# matrix.net
KiCad netlist of a schematic drawn in Altium Designer
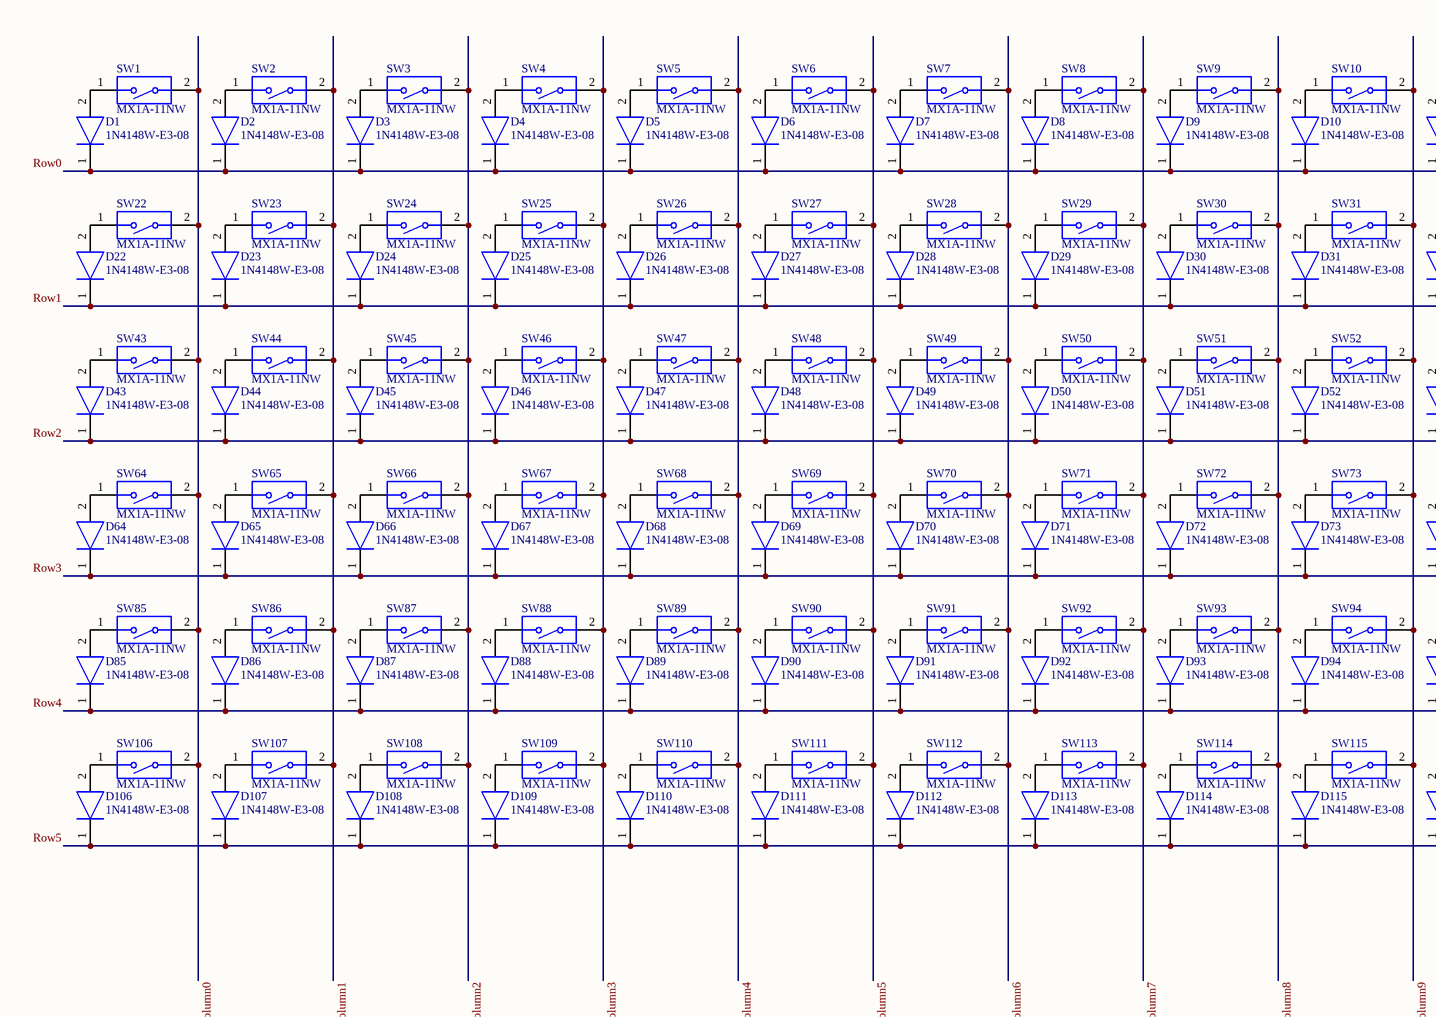
[diagram p0: matrix.SchDoc, left]
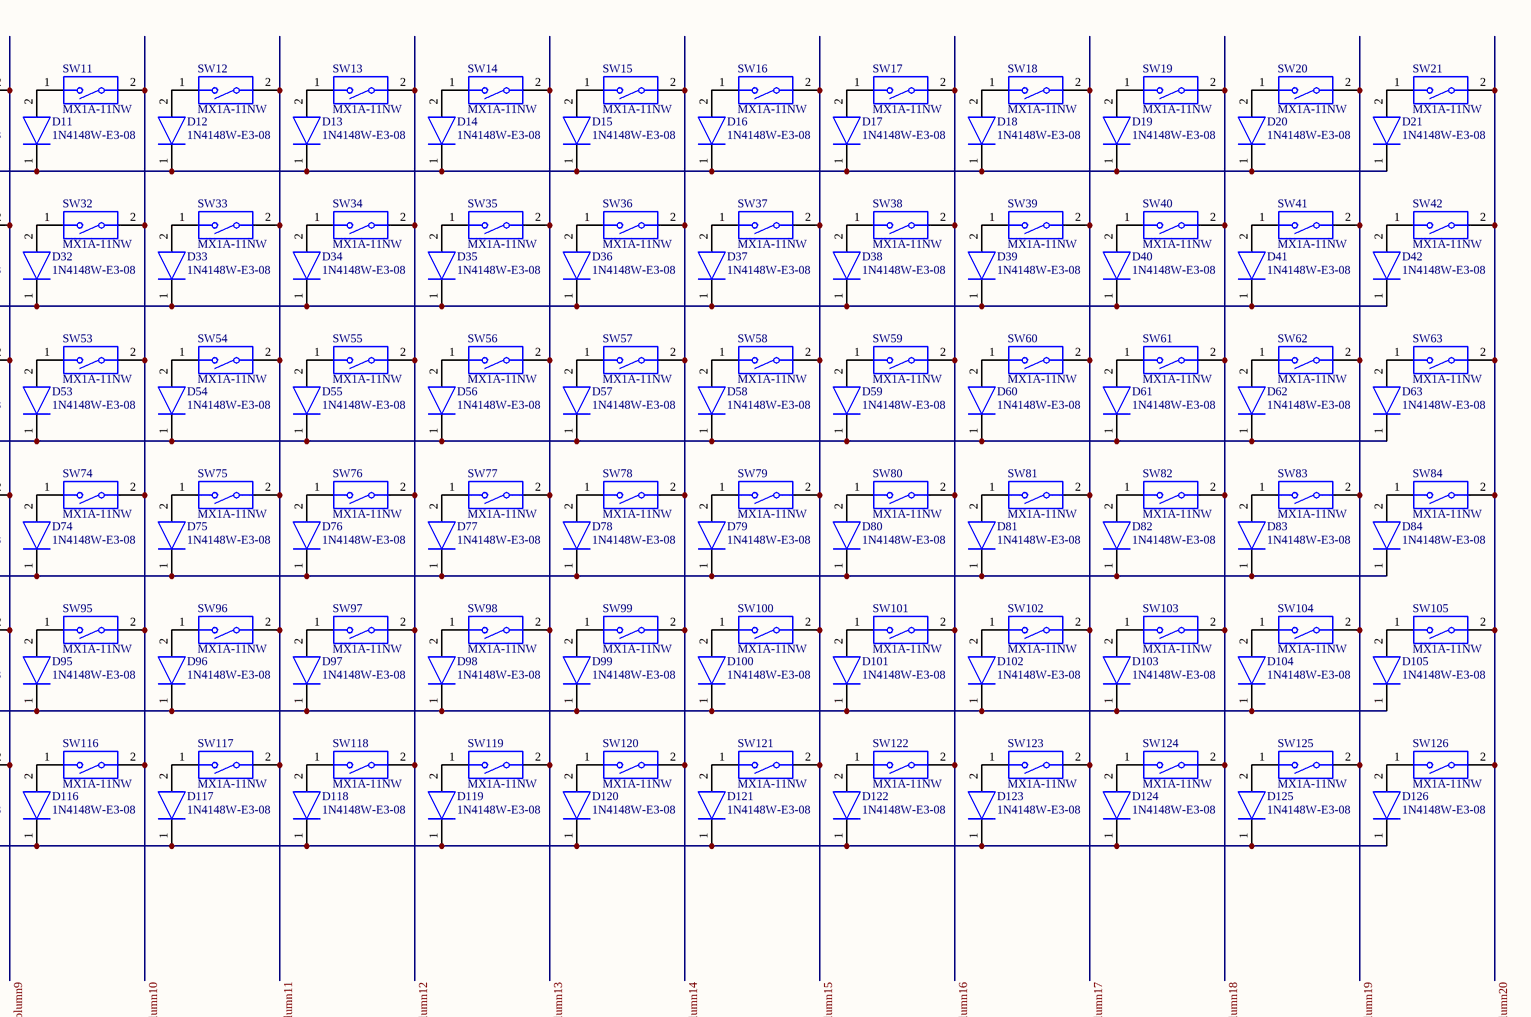
[diagram p1: matrix.SchDoc, right]

(export (version "E")
  (design (tool "Eeschema 10.0.6"))
  (components
    (comp (ref "D1")
      (value "1N4148W-E3-08")
      (footprint "SamacSys:SOD3716X135N")
      (description "Diode")
      (fields (field (name "MOUSER PART NUMBER") "78-1N4148W-E3-08"))
      (libsource (lib "*") (part "1N4148W-E3-08"))
    )
    (comp (ref "D2")
      (value "1N4148W-E3-08")
      (footprint "SamacSys:SOD3716X135N")
      (description "Diode")
      (fields (field (name "MOUSER PART NUMBER") "78-1N4148W-E3-08"))
      (libsource (lib "*") (part "1N4148W-E3-08"))
    )
    (comp (ref "D3")
      (value "1N4148W-E3-08")
      (footprint "SamacSys:SOD3716X135N")
      (description "Diode")
      (fields (field (name "MOUSER PART NUMBER") "78-1N4148W-E3-08"))
      (libsource (lib "*") (part "1N4148W-E3-08"))
    )
    (comp (ref "D4")
      (value "1N4148W-E3-08")
      (footprint "SamacSys:SOD3716X135N")
      (description "Diode")
      (fields (field (name "MOUSER PART NUMBER") "78-1N4148W-E3-08"))
      (libsource (lib "*") (part "1N4148W-E3-08"))
    )
    (comp (ref "D5")
      (value "1N4148W-E3-08")
      (footprint "SamacSys:SOD3716X135N")
      (description "Diode")
      (fields (field (name "MOUSER PART NUMBER") "78-1N4148W-E3-08"))
      (libsource (lib "*") (part "1N4148W-E3-08"))
    )
    (comp (ref "D6")
      (value "1N4148W-E3-08")
      (footprint "SamacSys:SOD3716X135N")
      (description "Diode")
      (fields (field (name "MOUSER PART NUMBER") "78-1N4148W-E3-08"))
      (libsource (lib "*") (part "1N4148W-E3-08"))
    )
    (comp (ref "D7")
      (value "1N4148W-E3-08")
      (footprint "SamacSys:SOD3716X135N")
      (description "Diode")
      (fields (field (name "MOUSER PART NUMBER") "78-1N4148W-E3-08"))
      (libsource (lib "*") (part "1N4148W-E3-08"))
    )
    (comp (ref "D8")
      (value "1N4148W-E3-08")
      (footprint "SamacSys:SOD3716X135N")
      (description "Diode")
      (fields (field (name "MOUSER PART NUMBER") "78-1N4148W-E3-08"))
      (libsource (lib "*") (part "1N4148W-E3-08"))
    )
    (comp (ref "D9")
      (value "1N4148W-E3-08")
      (footprint "SamacSys:SOD3716X135N")
      (description "Diode")
      (fields (field (name "MOUSER PART NUMBER") "78-1N4148W-E3-08"))
      (libsource (lib "*") (part "1N4148W-E3-08"))
    )
    (comp (ref "D10")
      (value "1N4148W-E3-08")
      (footprint "SamacSys:SOD3716X135N")
      (description "Diode")
      (fields (field (name "MOUSER PART NUMBER") "78-1N4148W-E3-08"))
      (libsource (lib "*") (part "1N4148W-E3-08"))
    )
    (comp (ref "D11")
      (value "1N4148W-E3-08")
      (footprint "SamacSys:SOD3716X135N")
      (description "Diode")
      (fields (field (name "MOUSER PART NUMBER") "78-1N4148W-E3-08"))
      (libsource (lib "*") (part "1N4148W-E3-08"))
    )
    (comp (ref "D12")
      (value "1N4148W-E3-08")
      (footprint "SamacSys:SOD3716X135N")
      (description "Diode")
      (fields (field (name "MOUSER PART NUMBER") "78-1N4148W-E3-08"))
      (libsource (lib "*") (part "1N4148W-E3-08"))
    )
    (comp (ref "D13")
      (value "1N4148W-E3-08")
      (footprint "SamacSys:SOD3716X135N")
      (description "Diode")
      (fields (field (name "MOUSER PART NUMBER") "78-1N4148W-E3-08"))
      (libsource (lib "*") (part "1N4148W-E3-08"))
    )
    (comp (ref "D14")
      (value "1N4148W-E3-08")
      (footprint "SamacSys:SOD3716X135N")
      (description "Diode")
      (fields (field (name "MOUSER PART NUMBER") "78-1N4148W-E3-08"))
      (libsource (lib "*") (part "1N4148W-E3-08"))
    )
    (comp (ref "D15")
      (value "1N4148W-E3-08")
      (footprint "SamacSys:SOD3716X135N")
      (description "Diode")
      (fields (field (name "MOUSER PART NUMBER") "78-1N4148W-E3-08"))
      (libsource (lib "*") (part "1N4148W-E3-08"))
    )
    (comp (ref "D16")
      (value "1N4148W-E3-08")
      (footprint "SamacSys:SOD3716X135N")
      (description "Diode")
      (fields (field (name "MOUSER PART NUMBER") "78-1N4148W-E3-08"))
      (libsource (lib "*") (part "1N4148W-E3-08"))
    )
    (comp (ref "D17")
      (value "1N4148W-E3-08")
      (footprint "SamacSys:SOD3716X135N")
      (description "Diode")
      (fields (field (name "MOUSER PART NUMBER") "78-1N4148W-E3-08"))
      (libsource (lib "*") (part "1N4148W-E3-08"))
    )
    (comp (ref "D18")
      (value "1N4148W-E3-08")
      (footprint "SamacSys:SOD3716X135N")
      (description "Diode")
      (fields (field (name "MOUSER PART NUMBER") "78-1N4148W-E3-08"))
      (libsource (lib "*") (part "1N4148W-E3-08"))
    )
    (comp (ref "D19")
      (value "1N4148W-E3-08")
      (footprint "SamacSys:SOD3716X135N")
      (description "Diode")
      (fields (field (name "MOUSER PART NUMBER") "78-1N4148W-E3-08"))
      (libsource (lib "*") (part "1N4148W-E3-08"))
    )
    (comp (ref "D20")
      (value "1N4148W-E3-08")
      (footprint "SamacSys:SOD3716X135N")
      (description "Diode")
      (fields (field (name "MOUSER PART NUMBER") "78-1N4148W-E3-08"))
      (libsource (lib "*") (part "1N4148W-E3-08"))
    )
    (comp (ref "D21")
      (value "1N4148W-E3-08")
      (footprint "SamacSys:SOD3716X135N")
      (description "Diode")
      (fields (field (name "MOUSER PART NUMBER") "78-1N4148W-E3-08"))
      (libsource (lib "*") (part "1N4148W-E3-08"))
    )
    (comp (ref "D22")
      (value "1N4148W-E3-08")
      (footprint "SamacSys:SOD3716X135N")
      (description "Diode")
      (fields (field (name "MOUSER PART NUMBER") "78-1N4148W-E3-08"))
      (libsource (lib "*") (part "1N4148W-E3-08"))
    )
    (comp (ref "D23")
      (value "1N4148W-E3-08")
      (footprint "SamacSys:SOD3716X135N")
      (description "Diode")
      (fields (field (name "MOUSER PART NUMBER") "78-1N4148W-E3-08"))
      (libsource (lib "*") (part "1N4148W-E3-08"))
    )
    (comp (ref "D24")
      (value "1N4148W-E3-08")
      (footprint "SamacSys:SOD3716X135N")
      (description "Diode")
      (fields (field (name "MOUSER PART NUMBER") "78-1N4148W-E3-08"))
      (libsource (lib "*") (part "1N4148W-E3-08"))
    )
    (comp (ref "D25")
      (value "1N4148W-E3-08")
      (footprint "SamacSys:SOD3716X135N")
      (description "Diode")
      (fields (field (name "MOUSER PART NUMBER") "78-1N4148W-E3-08"))
      (libsource (lib "*") (part "1N4148W-E3-08"))
    )
    (comp (ref "D26")
      (value "1N4148W-E3-08")
      (footprint "SamacSys:SOD3716X135N")
      (description "Diode")
      (fields (field (name "MOUSER PART NUMBER") "78-1N4148W-E3-08"))
      (libsource (lib "*") (part "1N4148W-E3-08"))
    )
    (comp (ref "D27")
      (value "1N4148W-E3-08")
      (footprint "SamacSys:SOD3716X135N")
      (description "Diode")
      (fields (field (name "MOUSER PART NUMBER") "78-1N4148W-E3-08"))
      (libsource (lib "*") (part "1N4148W-E3-08"))
    )
    (comp (ref "D28")
      (value "1N4148W-E3-08")
      (footprint "SamacSys:SOD3716X135N")
      (description "Diode")
      (fields (field (name "MOUSER PART NUMBER") "78-1N4148W-E3-08"))
      (libsource (lib "*") (part "1N4148W-E3-08"))
    )
    (comp (ref "D29")
      (value "1N4148W-E3-08")
      (footprint "SamacSys:SOD3716X135N")
      (description "Diode")
      (fields (field (name "MOUSER PART NUMBER") "78-1N4148W-E3-08"))
      (libsource (lib "*") (part "1N4148W-E3-08"))
    )
    (comp (ref "D30")
      (value "1N4148W-E3-08")
      (footprint "SamacSys:SOD3716X135N")
      (description "Diode")
      (fields (field (name "MOUSER PART NUMBER") "78-1N4148W-E3-08"))
      (libsource (lib "*") (part "1N4148W-E3-08"))
    )
    (comp (ref "D31")
      (value "1N4148W-E3-08")
      (footprint "SamacSys:SOD3716X135N")
      (description "Diode")
      (fields (field (name "MOUSER PART NUMBER") "78-1N4148W-E3-08"))
      (libsource (lib "*") (part "1N4148W-E3-08"))
    )
    (comp (ref "D32")
      (value "1N4148W-E3-08")
      (footprint "SamacSys:SOD3716X135N")
      (description "Diode")
      (fields (field (name "MOUSER PART NUMBER") "78-1N4148W-E3-08"))
      (libsource (lib "*") (part "1N4148W-E3-08"))
    )
    (comp (ref "D33")
      (value "1N4148W-E3-08")
      (footprint "SamacSys:SOD3716X135N")
      (description "Diode")
      (fields (field (name "MOUSER PART NUMBER") "78-1N4148W-E3-08"))
      (libsource (lib "*") (part "1N4148W-E3-08"))
    )
    (comp (ref "D34")
      (value "1N4148W-E3-08")
      (footprint "SamacSys:SOD3716X135N")
      (description "Diode")
      (fields (field (name "MOUSER PART NUMBER") "78-1N4148W-E3-08"))
      (libsource (lib "*") (part "1N4148W-E3-08"))
    )
    (comp (ref "D35")
      (value "1N4148W-E3-08")
      (footprint "SamacSys:SOD3716X135N")
      (description "Diode")
      (fields (field (name "MOUSER PART NUMBER") "78-1N4148W-E3-08"))
      (libsource (lib "*") (part "1N4148W-E3-08"))
    )
    (comp (ref "D36")
      (value "1N4148W-E3-08")
      (footprint "SamacSys:SOD3716X135N")
      (description "Diode")
      (fields (field (name "MOUSER PART NUMBER") "78-1N4148W-E3-08"))
      (libsource (lib "*") (part "1N4148W-E3-08"))
    )
    (comp (ref "D37")
      (value "1N4148W-E3-08")
      (footprint "SamacSys:SOD3716X135N")
      (description "Diode")
      (fields (field (name "MOUSER PART NUMBER") "78-1N4148W-E3-08"))
      (libsource (lib "*") (part "1N4148W-E3-08"))
    )
    (comp (ref "D38")
      (value "1N4148W-E3-08")
      (footprint "SamacSys:SOD3716X135N")
      (description "Diode")
      (fields (field (name "MOUSER PART NUMBER") "78-1N4148W-E3-08"))
      (libsource (lib "*") (part "1N4148W-E3-08"))
    )
    (comp (ref "D39")
      (value "1N4148W-E3-08")
      (footprint "SamacSys:SOD3716X135N")
      (description "Diode")
      (fields (field (name "MOUSER PART NUMBER") "78-1N4148W-E3-08"))
      (libsource (lib "*") (part "1N4148W-E3-08"))
    )
    (comp (ref "D40")
      (value "1N4148W-E3-08")
      (footprint "SamacSys:SOD3716X135N")
      (description "Diode")
      (fields (field (name "MOUSER PART NUMBER") "78-1N4148W-E3-08"))
      (libsource (lib "*") (part "1N4148W-E3-08"))
    )
    (comp (ref "D41")
      (value "1N4148W-E3-08")
      (footprint "SamacSys:SOD3716X135N")
      (description "Diode")
      (fields (field (name "MOUSER PART NUMBER") "78-1N4148W-E3-08"))
      (libsource (lib "*") (part "1N4148W-E3-08"))
    )
    (comp (ref "D42")
      (value "1N4148W-E3-08")
      (footprint "SamacSys:SOD3716X135N")
      (description "Diode")
      (fields (field (name "MOUSER PART NUMBER") "78-1N4148W-E3-08"))
      (libsource (lib "*") (part "1N4148W-E3-08"))
    )
    (comp (ref "D43")
      (value "1N4148W-E3-08")
      (footprint "SamacSys:SOD3716X135N")
      (description "Diode")
      (fields (field (name "MOUSER PART NUMBER") "78-1N4148W-E3-08"))
      (libsource (lib "*") (part "1N4148W-E3-08"))
    )
    (comp (ref "D44")
      (value "1N4148W-E3-08")
      (footprint "SamacSys:SOD3716X135N")
      (description "Diode")
      (fields (field (name "MOUSER PART NUMBER") "78-1N4148W-E3-08"))
      (libsource (lib "*") (part "1N4148W-E3-08"))
    )
    (comp (ref "D45")
      (value "1N4148W-E3-08")
      (footprint "SamacSys:SOD3716X135N")
      (description "Diode")
      (fields (field (name "MOUSER PART NUMBER") "78-1N4148W-E3-08"))
      (libsource (lib "*") (part "1N4148W-E3-08"))
    )
    (comp (ref "D46")
      (value "1N4148W-E3-08")
      (footprint "SamacSys:SOD3716X135N")
      (description "Diode")
      (fields (field (name "MOUSER PART NUMBER") "78-1N4148W-E3-08"))
      (libsource (lib "*") (part "1N4148W-E3-08"))
    )
    (comp (ref "D47")
      (value "1N4148W-E3-08")
      (footprint "SamacSys:SOD3716X135N")
      (description "Diode")
      (fields (field (name "MOUSER PART NUMBER") "78-1N4148W-E3-08"))
      (libsource (lib "*") (part "1N4148W-E3-08"))
    )
    (comp (ref "D48")
      (value "1N4148W-E3-08")
      (footprint "SamacSys:SOD3716X135N")
      (description "Diode")
      (fields (field (name "MOUSER PART NUMBER") "78-1N4148W-E3-08"))
      (libsource (lib "*") (part "1N4148W-E3-08"))
    )
    (comp (ref "D49")
      (value "1N4148W-E3-08")
      (footprint "SamacSys:SOD3716X135N")
      (description "Diode")
      (fields (field (name "MOUSER PART NUMBER") "78-1N4148W-E3-08"))
      (libsource (lib "*") (part "1N4148W-E3-08"))
    )
    (comp (ref "D50")
      (value "1N4148W-E3-08")
      (footprint "SamacSys:SOD3716X135N")
      (description "Diode")
      (fields (field (name "MOUSER PART NUMBER") "78-1N4148W-E3-08"))
      (libsource (lib "*") (part "1N4148W-E3-08"))
    )
    (comp (ref "D51")
      (value "1N4148W-E3-08")
      (footprint "SamacSys:SOD3716X135N")
      (description "Diode")
      (fields (field (name "MOUSER PART NUMBER") "78-1N4148W-E3-08"))
      (libsource (lib "*") (part "1N4148W-E3-08"))
    )
    (comp (ref "D52")
      (value "1N4148W-E3-08")
      (footprint "SamacSys:SOD3716X135N")
      (description "Diode")
      (fields (field (name "MOUSER PART NUMBER") "78-1N4148W-E3-08"))
      (libsource (lib "*") (part "1N4148W-E3-08"))
    )
    (comp (ref "D53")
      (value "1N4148W-E3-08")
      (footprint "SamacSys:SOD3716X135N")
      (description "Diode")
      (fields (field (name "MOUSER PART NUMBER") "78-1N4148W-E3-08"))
      (libsource (lib "*") (part "1N4148W-E3-08"))
    )
    (comp (ref "D54")
      (value "1N4148W-E3-08")
      (footprint "SamacSys:SOD3716X135N")
      (description "Diode")
      (fields (field (name "MOUSER PART NUMBER") "78-1N4148W-E3-08"))
      (libsource (lib "*") (part "1N4148W-E3-08"))
    )
    (comp (ref "D55")
      (value "1N4148W-E3-08")
      (footprint "SamacSys:SOD3716X135N")
      (description "Diode")
      (fields (field (name "MOUSER PART NUMBER") "78-1N4148W-E3-08"))
      (libsource (lib "*") (part "1N4148W-E3-08"))
    )
    (comp (ref "D56")
      (value "1N4148W-E3-08")
      (footprint "SamacSys:SOD3716X135N")
      (description "Diode")
      (fields (field (name "MOUSER PART NUMBER") "78-1N4148W-E3-08"))
      (libsource (lib "*") (part "1N4148W-E3-08"))
    )
    (comp (ref "D57")
      (value "1N4148W-E3-08")
      (footprint "SamacSys:SOD3716X135N")
      (description "Diode")
      (fields (field (name "MOUSER PART NUMBER") "78-1N4148W-E3-08"))
      (libsource (lib "*") (part "1N4148W-E3-08"))
    )
    (comp (ref "D58")
      (value "1N4148W-E3-08")
      (footprint "SamacSys:SOD3716X135N")
      (description "Diode")
      (fields (field (name "MOUSER PART NUMBER") "78-1N4148W-E3-08"))
      (libsource (lib "*") (part "1N4148W-E3-08"))
    )
    (comp (ref "D59")
      (value "1N4148W-E3-08")
      (footprint "SamacSys:SOD3716X135N")
      (description "Diode")
      (fields (field (name "MOUSER PART NUMBER") "78-1N4148W-E3-08"))
      (libsource (lib "*") (part "1N4148W-E3-08"))
    )
    (comp (ref "D60")
      (value "1N4148W-E3-08")
      (footprint "SamacSys:SOD3716X135N")
      (description "Diode")
      (fields (field (name "MOUSER PART NUMBER") "78-1N4148W-E3-08"))
      (libsource (lib "*") (part "1N4148W-E3-08"))
    )
    (comp (ref "D61")
      (value "1N4148W-E3-08")
      (footprint "SamacSys:SOD3716X135N")
      (description "Diode")
      (fields (field (name "MOUSER PART NUMBER") "78-1N4148W-E3-08"))
      (libsource (lib "*") (part "1N4148W-E3-08"))
    )
    (comp (ref "D62")
      (value "1N4148W-E3-08")
      (footprint "SamacSys:SOD3716X135N")
      (description "Diode")
      (fields (field (name "MOUSER PART NUMBER") "78-1N4148W-E3-08"))
      (libsource (lib "*") (part "1N4148W-E3-08"))
    )
    (comp (ref "D63")
      (value "1N4148W-E3-08")
      (footprint "SamacSys:SOD3716X135N")
      (description "Diode")
      (fields (field (name "MOUSER PART NUMBER") "78-1N4148W-E3-08"))
      (libsource (lib "*") (part "1N4148W-E3-08"))
    )
    (comp (ref "D64")
      (value "1N4148W-E3-08")
      (footprint "SamacSys:SOD3716X135N")
      (description "Diode")
      (fields (field (name "MOUSER PART NUMBER") "78-1N4148W-E3-08"))
      (libsource (lib "*") (part "1N4148W-E3-08"))
    )
    (comp (ref "D65")
      (value "1N4148W-E3-08")
      (footprint "SamacSys:SOD3716X135N")
      (description "Diode")
      (fields (field (name "MOUSER PART NUMBER") "78-1N4148W-E3-08"))
      (libsource (lib "*") (part "1N4148W-E3-08"))
    )
    (comp (ref "D66")
      (value "1N4148W-E3-08")
      (footprint "SamacSys:SOD3716X135N")
      (description "Diode")
      (fields (field (name "MOUSER PART NUMBER") "78-1N4148W-E3-08"))
      (libsource (lib "*") (part "1N4148W-E3-08"))
    )
    (comp (ref "D67")
      (value "1N4148W-E3-08")
      (footprint "SamacSys:SOD3716X135N")
      (description "Diode")
      (fields (field (name "MOUSER PART NUMBER") "78-1N4148W-E3-08"))
      (libsource (lib "*") (part "1N4148W-E3-08"))
    )
    (comp (ref "D68")
      (value "1N4148W-E3-08")
      (footprint "SamacSys:SOD3716X135N")
      (description "Diode")
      (fields (field (name "MOUSER PART NUMBER") "78-1N4148W-E3-08"))
      (libsource (lib "*") (part "1N4148W-E3-08"))
    )
    (comp (ref "D69")
      (value "1N4148W-E3-08")
      (footprint "SamacSys:SOD3716X135N")
      (description "Diode")
      (fields (field (name "MOUSER PART NUMBER") "78-1N4148W-E3-08"))
      (libsource (lib "*") (part "1N4148W-E3-08"))
    )
    (comp (ref "D70")
      (value "1N4148W-E3-08")
      (footprint "SamacSys:SOD3716X135N")
      (description "Diode")
      (fields (field (name "MOUSER PART NUMBER") "78-1N4148W-E3-08"))
      (libsource (lib "*") (part "1N4148W-E3-08"))
    )
    (comp (ref "D71")
      (value "1N4148W-E3-08")
      (footprint "SamacSys:SOD3716X135N")
      (description "Diode")
      (fields (field (name "MOUSER PART NUMBER") "78-1N4148W-E3-08"))
      (libsource (lib "*") (part "1N4148W-E3-08"))
    )
    (comp (ref "D72")
      (value "1N4148W-E3-08")
      (footprint "SamacSys:SOD3716X135N")
      (description "Diode")
      (fields (field (name "MOUSER PART NUMBER") "78-1N4148W-E3-08"))
      (libsource (lib "*") (part "1N4148W-E3-08"))
    )
    (comp (ref "D73")
      (value "1N4148W-E3-08")
      (footprint "SamacSys:SOD3716X135N")
      (description "Diode")
      (fields (field (name "MOUSER PART NUMBER") "78-1N4148W-E3-08"))
      (libsource (lib "*") (part "1N4148W-E3-08"))
    )
    (comp (ref "D74")
      (value "1N4148W-E3-08")
      (footprint "SamacSys:SOD3716X135N")
      (description "Diode")
      (fields (field (name "MOUSER PART NUMBER") "78-1N4148W-E3-08"))
      (libsource (lib "*") (part "1N4148W-E3-08"))
    )
    (comp (ref "D75")
      (value "1N4148W-E3-08")
      (footprint "SamacSys:SOD3716X135N")
      (description "Diode")
      (fields (field (name "MOUSER PART NUMBER") "78-1N4148W-E3-08"))
      (libsource (lib "*") (part "1N4148W-E3-08"))
    )
    (comp (ref "D76")
      (value "1N4148W-E3-08")
      (footprint "SamacSys:SOD3716X135N")
      (description "Diode")
      (fields (field (name "MOUSER PART NUMBER") "78-1N4148W-E3-08"))
      (libsource (lib "*") (part "1N4148W-E3-08"))
    )
    (comp (ref "D77")
      (value "1N4148W-E3-08")
      (footprint "SamacSys:SOD3716X135N")
      (description "Diode")
      (fields (field (name "MOUSER PART NUMBER") "78-1N4148W-E3-08"))
      (libsource (lib "*") (part "1N4148W-E3-08"))
    )
    (comp (ref "D78")
      (value "1N4148W-E3-08")
      (footprint "SamacSys:SOD3716X135N")
      (description "Diode")
      (fields (field (name "MOUSER PART NUMBER") "78-1N4148W-E3-08"))
      (libsource (lib "*") (part "1N4148W-E3-08"))
    )
    (comp (ref "D79")
      (value "1N4148W-E3-08")
      (footprint "SamacSys:SOD3716X135N")
      (description "Diode")
      (fields (field (name "MOUSER PART NUMBER") "78-1N4148W-E3-08"))
      (libsource (lib "*") (part "1N4148W-E3-08"))
    )
    (comp (ref "D80")
      (value "1N4148W-E3-08")
      (footprint "SamacSys:SOD3716X135N")
      (description "Diode")
      (fields (field (name "MOUSER PART NUMBER") "78-1N4148W-E3-08"))
      (libsource (lib "*") (part "1N4148W-E3-08"))
    )
    (comp (ref "D81")
      (value "1N4148W-E3-08")
      (footprint "SamacSys:SOD3716X135N")
      (description "Diode")
      (fields (field (name "MOUSER PART NUMBER") "78-1N4148W-E3-08"))
      (libsource (lib "*") (part "1N4148W-E3-08"))
    )
    (comp (ref "D82")
      (value "1N4148W-E3-08")
      (footprint "SamacSys:SOD3716X135N")
      (description "Diode")
      (fields (field (name "MOUSER PART NUMBER") "78-1N4148W-E3-08"))
      (libsource (lib "*") (part "1N4148W-E3-08"))
    )
    (comp (ref "D83")
      (value "1N4148W-E3-08")
      (footprint "SamacSys:SOD3716X135N")
      (description "Diode")
      (fields (field (name "MOUSER PART NUMBER") "78-1N4148W-E3-08"))
      (libsource (lib "*") (part "1N4148W-E3-08"))
    )
    (comp (ref "D84")
      (value "1N4148W-E3-08")
      (footprint "SamacSys:SOD3716X135N")
      (description "Diode")
      (fields (field (name "MOUSER PART NUMBER") "78-1N4148W-E3-08"))
      (libsource (lib "*") (part "1N4148W-E3-08"))
    )
    (comp (ref "D85")
      (value "1N4148W-E3-08")
      (footprint "SamacSys:SOD3716X135N")
      (description "Diode")
      (fields (field (name "MOUSER PART NUMBER") "78-1N4148W-E3-08"))
      (libsource (lib "*") (part "1N4148W-E3-08"))
    )
    (comp (ref "D86")
      (value "1N4148W-E3-08")
      (footprint "SamacSys:SOD3716X135N")
      (description "Diode")
      (fields (field (name "MOUSER PART NUMBER") "78-1N4148W-E3-08"))
      (libsource (lib "*") (part "1N4148W-E3-08"))
    )
    (comp (ref "D87")
      (value "1N4148W-E3-08")
      (footprint "SamacSys:SOD3716X135N")
      (description "Diode")
      (fields (field (name "MOUSER PART NUMBER") "78-1N4148W-E3-08"))
      (libsource (lib "*") (part "1N4148W-E3-08"))
    )
    (comp (ref "D88")
      (value "1N4148W-E3-08")
      (footprint "SamacSys:SOD3716X135N")
      (description "Diode")
      (fields (field (name "MOUSER PART NUMBER") "78-1N4148W-E3-08"))
      (libsource (lib "*") (part "1N4148W-E3-08"))
    )
    (comp (ref "D89")
      (value "1N4148W-E3-08")
      (footprint "SamacSys:SOD3716X135N")
      (description "Diode")
      (fields (field (name "MOUSER PART NUMBER") "78-1N4148W-E3-08"))
      (libsource (lib "*") (part "1N4148W-E3-08"))
    )
    (comp (ref "D90")
      (value "1N4148W-E3-08")
      (footprint "SamacSys:SOD3716X135N")
      (description "Diode")
      (fields (field (name "MOUSER PART NUMBER") "78-1N4148W-E3-08"))
      (libsource (lib "*") (part "1N4148W-E3-08"))
    )
    (comp (ref "D91")
      (value "1N4148W-E3-08")
      (footprint "SamacSys:SOD3716X135N")
      (description "Diode")
      (fields (field (name "MOUSER PART NUMBER") "78-1N4148W-E3-08"))
      (libsource (lib "*") (part "1N4148W-E3-08"))
    )
    (comp (ref "D92")
      (value "1N4148W-E3-08")
      (footprint "SamacSys:SOD3716X135N")
      (description "Diode")
      (fields (field (name "MOUSER PART NUMBER") "78-1N4148W-E3-08"))
      (libsource (lib "*") (part "1N4148W-E3-08"))
    )
    (comp (ref "D93")
      (value "1N4148W-E3-08")
      (footprint "SamacSys:SOD3716X135N")
      (description "Diode")
      (fields (field (name "MOUSER PART NUMBER") "78-1N4148W-E3-08"))
      (libsource (lib "*") (part "1N4148W-E3-08"))
    )
    (comp (ref "D94")
      (value "1N4148W-E3-08")
      (footprint "SamacSys:SOD3716X135N")
      (description "Diode")
      (fields (field (name "MOUSER PART NUMBER") "78-1N4148W-E3-08"))
      (libsource (lib "*") (part "1N4148W-E3-08"))
    )
    (comp (ref "D95")
      (value "1N4148W-E3-08")
      (footprint "SamacSys:SOD3716X135N")
      (description "Diode")
      (fields (field (name "MOUSER PART NUMBER") "78-1N4148W-E3-08"))
      (libsource (lib "*") (part "1N4148W-E3-08"))
    )
    (comp (ref "D96")
      (value "1N4148W-E3-08")
      (footprint "SamacSys:SOD3716X135N")
      (description "Diode")
      (fields (field (name "MOUSER PART NUMBER") "78-1N4148W-E3-08"))
      (libsource (lib "*") (part "1N4148W-E3-08"))
    )
    (comp (ref "D97")
      (value "1N4148W-E3-08")
      (footprint "SamacSys:SOD3716X135N")
      (description "Diode")
      (fields (field (name "MOUSER PART NUMBER") "78-1N4148W-E3-08"))
      (libsource (lib "*") (part "1N4148W-E3-08"))
    )
    (comp (ref "D98")
      (value "1N4148W-E3-08")
      (footprint "SamacSys:SOD3716X135N")
      (description "Diode")
      (fields (field (name "MOUSER PART NUMBER") "78-1N4148W-E3-08"))
      (libsource (lib "*") (part "1N4148W-E3-08"))
    )
    (comp (ref "D99")
      (value "1N4148W-E3-08")
      (footprint "SamacSys:SOD3716X135N")
      (description "Diode")
      (fields (field (name "MOUSER PART NUMBER") "78-1N4148W-E3-08"))
      (libsource (lib "*") (part "1N4148W-E3-08"))
    )
    (comp (ref "D100")
      (value "1N4148W-E3-08")
      (footprint "SamacSys:SOD3716X135N")
      (description "Diode")
      (fields (field (name "MOUSER PART NUMBER") "78-1N4148W-E3-08"))
      (libsource (lib "*") (part "1N4148W-E3-08"))
    )
    (comp (ref "D101")
      (value "1N4148W-E3-08")
      (footprint "SamacSys:SOD3716X135N")
      (description "Diode")
      (fields (field (name "MOUSER PART NUMBER") "78-1N4148W-E3-08"))
      (libsource (lib "*") (part "1N4148W-E3-08"))
    )
    (comp (ref "D102")
      (value "1N4148W-E3-08")
      (footprint "SamacSys:SOD3716X135N")
      (description "Diode")
      (fields (field (name "MOUSER PART NUMBER") "78-1N4148W-E3-08"))
      (libsource (lib "*") (part "1N4148W-E3-08"))
    )
    (comp (ref "D103")
      (value "1N4148W-E3-08")
      (footprint "SamacSys:SOD3716X135N")
      (description "Diode")
      (fields (field (name "MOUSER PART NUMBER") "78-1N4148W-E3-08"))
      (libsource (lib "*") (part "1N4148W-E3-08"))
    )
    (comp (ref "D104")
      (value "1N4148W-E3-08")
      (footprint "SamacSys:SOD3716X135N")
      (description "Diode")
      (fields (field (name "MOUSER PART NUMBER") "78-1N4148W-E3-08"))
      (libsource (lib "*") (part "1N4148W-E3-08"))
    )
    (comp (ref "D105")
      (value "1N4148W-E3-08")
      (footprint "SamacSys:SOD3716X135N")
      (description "Diode")
      (fields (field (name "MOUSER PART NUMBER") "78-1N4148W-E3-08"))
      (libsource (lib "*") (part "1N4148W-E3-08"))
    )
    (comp (ref "D106")
      (value "1N4148W-E3-08")
      (footprint "SamacSys:SOD3716X135N")
      (description "Diode")
      (fields (field (name "MOUSER PART NUMBER") "78-1N4148W-E3-08"))
      (libsource (lib "*") (part "1N4148W-E3-08"))
    )
    (comp (ref "D107")
      (value "1N4148W-E3-08")
      (footprint "SamacSys:SOD3716X135N")
      (description "Diode")
      (fields (field (name "MOUSER PART NUMBER") "78-1N4148W-E3-08"))
      (libsource (lib "*") (part "1N4148W-E3-08"))
    )
    (comp (ref "D108")
      (value "1N4148W-E3-08")
      (footprint "SamacSys:SOD3716X135N")
      (description "Diode")
      (fields (field (name "MOUSER PART NUMBER") "78-1N4148W-E3-08"))
      (libsource (lib "*") (part "1N4148W-E3-08"))
    )
    (comp (ref "D109")
      (value "1N4148W-E3-08")
      (footprint "SamacSys:SOD3716X135N")
      (description "Diode")
      (fields (field (name "MOUSER PART NUMBER") "78-1N4148W-E3-08"))
      (libsource (lib "*") (part "1N4148W-E3-08"))
    )
    (comp (ref "D110")
      (value "1N4148W-E3-08")
      (footprint "SamacSys:SOD3716X135N")
      (description "Diode")
      (fields (field (name "MOUSER PART NUMBER") "78-1N4148W-E3-08"))
      (libsource (lib "*") (part "1N4148W-E3-08"))
    )
    (comp (ref "D111")
      (value "1N4148W-E3-08")
      (footprint "SamacSys:SOD3716X135N")
      (description "Diode")
      (fields (field (name "MOUSER PART NUMBER") "78-1N4148W-E3-08"))
      (libsource (lib "*") (part "1N4148W-E3-08"))
    )
    (comp (ref "D112")
      (value "1N4148W-E3-08")
      (footprint "SamacSys:SOD3716X135N")
      (description "Diode")
      (fields (field (name "MOUSER PART NUMBER") "78-1N4148W-E3-08"))
      (libsource (lib "*") (part "1N4148W-E3-08"))
    )
    (comp (ref "D113")
      (value "1N4148W-E3-08")
      (footprint "SamacSys:SOD3716X135N")
      (description "Diode")
      (fields (field (name "MOUSER PART NUMBER") "78-1N4148W-E3-08"))
      (libsource (lib "*") (part "1N4148W-E3-08"))
    )
    (comp (ref "D114")
      (value "1N4148W-E3-08")
      (footprint "SamacSys:SOD3716X135N")
      (description "Diode")
      (fields (field (name "MOUSER PART NUMBER") "78-1N4148W-E3-08"))
      (libsource (lib "*") (part "1N4148W-E3-08"))
    )
    (comp (ref "D115")
      (value "1N4148W-E3-08")
      (footprint "SamacSys:SOD3716X135N")
      (description "Diode")
      (fields (field (name "MOUSER PART NUMBER") "78-1N4148W-E3-08"))
      (libsource (lib "*") (part "1N4148W-E3-08"))
    )
    (comp (ref "D116")
      (value "1N4148W-E3-08")
      (footprint "SamacSys:SOD3716X135N")
      (description "Diode")
      (fields (field (name "MOUSER PART NUMBER") "78-1N4148W-E3-08"))
      (libsource (lib "*") (part "1N4148W-E3-08"))
    )
    (comp (ref "D117")
      (value "1N4148W-E3-08")
      (footprint "SamacSys:SOD3716X135N")
      (description "Diode")
      (fields (field (name "MOUSER PART NUMBER") "78-1N4148W-E3-08"))
      (libsource (lib "*") (part "1N4148W-E3-08"))
    )
    (comp (ref "D118")
      (value "1N4148W-E3-08")
      (footprint "SamacSys:SOD3716X135N")
      (description "Diode")
      (fields (field (name "MOUSER PART NUMBER") "78-1N4148W-E3-08"))
      (libsource (lib "*") (part "1N4148W-E3-08"))
    )
    (comp (ref "D119")
      (value "1N4148W-E3-08")
      (footprint "SamacSys:SOD3716X135N")
      (description "Diode")
      (fields (field (name "MOUSER PART NUMBER") "78-1N4148W-E3-08"))
      (libsource (lib "*") (part "1N4148W-E3-08"))
    )
    (comp (ref "D120")
      (value "1N4148W-E3-08")
      (footprint "SamacSys:SOD3716X135N")
      (description "Diode")
      (fields (field (name "MOUSER PART NUMBER") "78-1N4148W-E3-08"))
      (libsource (lib "*") (part "1N4148W-E3-08"))
    )
    (comp (ref "D121")
      (value "1N4148W-E3-08")
      (footprint "SamacSys:SOD3716X135N")
      (description "Diode")
      (fields (field (name "MOUSER PART NUMBER") "78-1N4148W-E3-08"))
      (libsource (lib "*") (part "1N4148W-E3-08"))
    )
    (comp (ref "D122")
      (value "1N4148W-E3-08")
      (footprint "SamacSys:SOD3716X135N")
      (description "Diode")
      (fields (field (name "MOUSER PART NUMBER") "78-1N4148W-E3-08"))
      (libsource (lib "*") (part "1N4148W-E3-08"))
    )
    (comp (ref "D123")
      (value "1N4148W-E3-08")
      (footprint "SamacSys:SOD3716X135N")
      (description "Diode")
      (fields (field (name "MOUSER PART NUMBER") "78-1N4148W-E3-08"))
      (libsource (lib "*") (part "1N4148W-E3-08"))
    )
    (comp (ref "D124")
      (value "1N4148W-E3-08")
      (footprint "SamacSys:SOD3716X135N")
      (description "Diode")
      (fields (field (name "MOUSER PART NUMBER") "78-1N4148W-E3-08"))
      (libsource (lib "*") (part "1N4148W-E3-08"))
    )
    (comp (ref "D125")
      (value "1N4148W-E3-08")
      (footprint "SamacSys:SOD3716X135N")
      (description "Diode")
      (fields (field (name "MOUSER PART NUMBER") "78-1N4148W-E3-08"))
      (libsource (lib "*") (part "1N4148W-E3-08"))
    )
    (comp (ref "D126")
      (value "1N4148W-E3-08")
      (footprint "SamacSys:SOD3716X135N")
      (description "Diode")
      (fields (field (name "MOUSER PART NUMBER") "78-1N4148W-E3-08"))
      (libsource (lib "*") (part "1N4148W-E3-08"))
    )
    (comp (ref "SW1")
      (value "MX1A-11NW")
      (footprint "CHRY-MX1A-11NW_V")
      (description "Keylock Switch, 12 V, -10 to 70 degC, 2-Pin THD, RoHS, Bulk")
      (fields (field (name "MANUFACTURER") "Cherry") (field (name "PART NO") "MX1A11NW"))
      (libsource (lib "mx1a-11nw") (part "CMP-2000-06786-1"))
    )
    (comp (ref "SW2")
      (value "MX1A-11NW")
      (footprint "CHRY-MX1A-11NW_V")
      (description "Keylock Switch, 12 V, -10 to 70 degC, 2-Pin THD, RoHS, Bulk")
      (fields (field (name "MANUFACTURER") "Cherry") (field (name "PART NO") "MX1A11NW"))
      (libsource (lib "mx1a-11nw") (part "CMP-2000-06786-1"))
    )
    (comp (ref "SW3")
      (value "MX1A-11NW")
      (footprint "CHRY-MX1A-11NW_V")
      (description "Keylock Switch, 12 V, -10 to 70 degC, 2-Pin THD, RoHS, Bulk")
      (fields (field (name "MANUFACTURER") "Cherry") (field (name "PART NO") "MX1A11NW"))
      (libsource (lib "mx1a-11nw") (part "CMP-2000-06786-1"))
    )
    (comp (ref "SW4")
      (value "MX1A-11NW")
      (footprint "CHRY-MX1A-11NW_V")
      (description "Keylock Switch, 12 V, -10 to 70 degC, 2-Pin THD, RoHS, Bulk")
      (fields (field (name "MANUFACTURER") "Cherry") (field (name "PART NO") "MX1A11NW"))
      (libsource (lib "mx1a-11nw") (part "CMP-2000-06786-1"))
    )
    (comp (ref "SW5")
      (value "MX1A-11NW")
      (footprint "CHRY-MX1A-11NW_V")
      (description "Keylock Switch, 12 V, -10 to 70 degC, 2-Pin THD, RoHS, Bulk")
      (fields (field (name "MANUFACTURER") "Cherry") (field (name "PART NO") "MX1A11NW"))
      (libsource (lib "mx1a-11nw") (part "CMP-2000-06786-1"))
    )
    (comp (ref "SW6")
      (value "MX1A-11NW")
      (footprint "CHRY-MX1A-11NW_V")
      (description "Keylock Switch, 12 V, -10 to 70 degC, 2-Pin THD, RoHS, Bulk")
      (fields (field (name "MANUFACTURER") "Cherry") (field (name "PART NO") "MX1A11NW"))
      (libsource (lib "mx1a-11nw") (part "CMP-2000-06786-1"))
    )
    (comp (ref "SW7")
      (value "MX1A-11NW")
      (footprint "CHRY-MX1A-11NW_V")
      (description "Keylock Switch, 12 V, -10 to 70 degC, 2-Pin THD, RoHS, Bulk")
      (fields (field (name "MANUFACTURER") "Cherry") (field (name "PART NO") "MX1A11NW"))
      (libsource (lib "mx1a-11nw") (part "CMP-2000-06786-1"))
    )
    (comp (ref "SW8")
      (value "MX1A-11NW")
      (footprint "CHRY-MX1A-11NW_V")
      (description "Keylock Switch, 12 V, -10 to 70 degC, 2-Pin THD, RoHS, Bulk")
      (fields (field (name "MANUFACTURER") "Cherry") (field (name "PART NO") "MX1A11NW"))
      (libsource (lib "mx1a-11nw") (part "CMP-2000-06786-1"))
    )
    (comp (ref "SW9")
      (value "MX1A-11NW")
      (footprint "CHRY-MX1A-11NW_V")
      (description "Keylock Switch, 12 V, -10 to 70 degC, 2-Pin THD, RoHS, Bulk")
      (fields (field (name "MANUFACTURER") "Cherry") (field (name "PART NO") "MX1A11NW"))
      (libsource (lib "mx1a-11nw") (part "CMP-2000-06786-1"))
    )
    (comp (ref "SW10")
      (value "MX1A-11NW")
      (footprint "CHRY-MX1A-11NW_V")
      (description "Keylock Switch, 12 V, -10 to 70 degC, 2-Pin THD, RoHS, Bulk")
      (fields (field (name "MANUFACTURER") "Cherry") (field (name "PART NO") "MX1A11NW"))
      (libsource (lib "mx1a-11nw") (part "CMP-2000-06786-1"))
    )
    (comp (ref "SW11")
      (value "MX1A-11NW")
      (footprint "CHRY-MX1A-11NW_V")
      (description "Keylock Switch, 12 V, -10 to 70 degC, 2-Pin THD, RoHS, Bulk")
      (fields (field (name "MANUFACTURER") "Cherry") (field (name "PART NO") "MX1A11NW"))
      (libsource (lib "mx1a-11nw") (part "CMP-2000-06786-1"))
    )
    (comp (ref "SW12")
      (value "MX1A-11NW")
      (footprint "CHRY-MX1A-11NW_V")
      (description "Keylock Switch, 12 V, -10 to 70 degC, 2-Pin THD, RoHS, Bulk")
      (fields (field (name "MANUFACTURER") "Cherry") (field (name "PART NO") "MX1A11NW"))
      (libsource (lib "mx1a-11nw") (part "CMP-2000-06786-1"))
    )
    (comp (ref "SW13")
      (value "MX1A-11NW")
      (footprint "CHRY-MX1A-11NW_V")
      (description "Keylock Switch, 12 V, -10 to 70 degC, 2-Pin THD, RoHS, Bulk")
      (fields (field (name "MANUFACTURER") "Cherry") (field (name "PART NO") "MX1A11NW"))
      (libsource (lib "mx1a-11nw") (part "CMP-2000-06786-1"))
    )
    (comp (ref "SW14")
      (value "MX1A-11NW")
      (footprint "CHRY-MX1A-11NW_V")
      (description "Keylock Switch, 12 V, -10 to 70 degC, 2-Pin THD, RoHS, Bulk")
      (fields (field (name "MANUFACTURER") "Cherry") (field (name "PART NO") "MX1A11NW"))
      (libsource (lib "mx1a-11nw") (part "CMP-2000-06786-1"))
    )
    (comp (ref "SW15")
      (value "MX1A-11NW")
      (footprint "CHRY-MX1A-11NW_V")
      (description "Keylock Switch, 12 V, -10 to 70 degC, 2-Pin THD, RoHS, Bulk")
      (fields (field (name "MANUFACTURER") "Cherry") (field (name "PART NO") "MX1A11NW"))
      (libsource (lib "mx1a-11nw") (part "CMP-2000-06786-1"))
    )
    (comp (ref "SW16")
      (value "MX1A-11NW")
      (footprint "CHRY-MX1A-11NW_V")
      (description "Keylock Switch, 12 V, -10 to 70 degC, 2-Pin THD, RoHS, Bulk")
      (fields (field (name "MANUFACTURER") "Cherry") (field (name "PART NO") "MX1A11NW"))
      (libsource (lib "mx1a-11nw") (part "CMP-2000-06786-1"))
    )
    (comp (ref "SW17")
      (value "MX1A-11NW")
      (footprint "CHRY-MX1A-11NW_V")
      (description "Keylock Switch, 12 V, -10 to 70 degC, 2-Pin THD, RoHS, Bulk")
      (fields (field (name "MANUFACTURER") "Cherry") (field (name "PART NO") "MX1A11NW"))
      (libsource (lib "mx1a-11nw") (part "CMP-2000-06786-1"))
    )
    (comp (ref "SW18")
      (value "MX1A-11NW")
      (footprint "CHRY-MX1A-11NW_V")
      (description "Keylock Switch, 12 V, -10 to 70 degC, 2-Pin THD, RoHS, Bulk")
      (fields (field (name "MANUFACTURER") "Cherry") (field (name "PART NO") "MX1A11NW"))
      (libsource (lib "mx1a-11nw") (part "CMP-2000-06786-1"))
    )
    (comp (ref "SW19")
      (value "MX1A-11NW")
      (footprint "CHRY-MX1A-11NW_V")
      (description "Keylock Switch, 12 V, -10 to 70 degC, 2-Pin THD, RoHS, Bulk")
      (fields (field (name "MANUFACTURER") "Cherry") (field (name "PART NO") "MX1A11NW"))
      (libsource (lib "mx1a-11nw") (part "CMP-2000-06786-1"))
    )
    (comp (ref "SW20")
      (value "MX1A-11NW")
      (footprint "CHRY-MX1A-11NW_V")
      (description "Keylock Switch, 12 V, -10 to 70 degC, 2-Pin THD, RoHS, Bulk")
      (fields (field (name "MANUFACTURER") "Cherry") (field (name "PART NO") "MX1A11NW"))
      (libsource (lib "mx1a-11nw") (part "CMP-2000-06786-1"))
    )
    (comp (ref "SW21")
      (value "MX1A-11NW")
      (footprint "CHRY-MX1A-11NW_V")
      (description "Keylock Switch, 12 V, -10 to 70 degC, 2-Pin THD, RoHS, Bulk")
      (fields (field (name "MANUFACTURER") "Cherry") (field (name "PART NO") "MX1A11NW"))
      (libsource (lib "mx1a-11nw") (part "CMP-2000-06786-1"))
    )
    (comp (ref "SW22")
      (value "MX1A-11NW")
      (footprint "CHRY-MX1A-11NW_V")
      (description "Keylock Switch, 12 V, -10 to 70 degC, 2-Pin THD, RoHS, Bulk")
      (fields (field (name "MANUFACTURER") "Cherry") (field (name "PART NO") "MX1A11NW"))
      (libsource (lib "mx1a-11nw") (part "CMP-2000-06786-1"))
    )
    (comp (ref "SW23")
      (value "MX1A-11NW")
      (footprint "CHRY-MX1A-11NW_V")
      (description "Keylock Switch, 12 V, -10 to 70 degC, 2-Pin THD, RoHS, Bulk")
      (fields (field (name "MANUFACTURER") "Cherry") (field (name "PART NO") "MX1A11NW"))
      (libsource (lib "mx1a-11nw") (part "CMP-2000-06786-1"))
    )
    (comp (ref "SW24")
      (value "MX1A-11NW")
      (footprint "CHRY-MX1A-11NW_V")
      (description "Keylock Switch, 12 V, -10 to 70 degC, 2-Pin THD, RoHS, Bulk")
      (fields (field (name "MANUFACTURER") "Cherry") (field (name "PART NO") "MX1A11NW"))
      (libsource (lib "mx1a-11nw") (part "CMP-2000-06786-1"))
    )
    (comp (ref "SW25")
      (value "MX1A-11NW")
      (footprint "CHRY-MX1A-11NW_V")
      (description "Keylock Switch, 12 V, -10 to 70 degC, 2-Pin THD, RoHS, Bulk")
      (fields (field (name "MANUFACTURER") "Cherry") (field (name "PART NO") "MX1A11NW"))
      (libsource (lib "mx1a-11nw") (part "CMP-2000-06786-1"))
    )
    (comp (ref "SW26")
      (value "MX1A-11NW")
      (footprint "CHRY-MX1A-11NW_V")
      (description "Keylock Switch, 12 V, -10 to 70 degC, 2-Pin THD, RoHS, Bulk")
      (fields (field (name "MANUFACTURER") "Cherry") (field (name "PART NO") "MX1A11NW"))
      (libsource (lib "mx1a-11nw") (part "CMP-2000-06786-1"))
    )
    (comp (ref "SW27")
      (value "MX1A-11NW")
      (footprint "CHRY-MX1A-11NW_V")
      (description "Keylock Switch, 12 V, -10 to 70 degC, 2-Pin THD, RoHS, Bulk")
      (fields (field (name "MANUFACTURER") "Cherry") (field (name "PART NO") "MX1A11NW"))
      (libsource (lib "mx1a-11nw") (part "CMP-2000-06786-1"))
    )
    (comp (ref "SW28")
      (value "MX1A-11NW")
      (footprint "CHRY-MX1A-11NW_V")
      (description "Keylock Switch, 12 V, -10 to 70 degC, 2-Pin THD, RoHS, Bulk")
      (fields (field (name "MANUFACTURER") "Cherry") (field (name "PART NO") "MX1A11NW"))
      (libsource (lib "mx1a-11nw") (part "CMP-2000-06786-1"))
    )
    (comp (ref "SW29")
      (value "MX1A-11NW")
      (footprint "CHRY-MX1A-11NW_V")
      (description "Keylock Switch, 12 V, -10 to 70 degC, 2-Pin THD, RoHS, Bulk")
      (fields (field (name "MANUFACTURER") "Cherry") (field (name "PART NO") "MX1A11NW"))
      (libsource (lib "mx1a-11nw") (part "CMP-2000-06786-1"))
    )
    (comp (ref "SW30")
      (value "MX1A-11NW")
      (footprint "CHRY-MX1A-11NW_V")
      (description "Keylock Switch, 12 V, -10 to 70 degC, 2-Pin THD, RoHS, Bulk")
      (fields (field (name "MANUFACTURER") "Cherry") (field (name "PART NO") "MX1A11NW"))
      (libsource (lib "mx1a-11nw") (part "CMP-2000-06786-1"))
    )
    (comp (ref "SW31")
      (value "MX1A-11NW")
      (footprint "CHRY-MX1A-11NW_V")
      (description "Keylock Switch, 12 V, -10 to 70 degC, 2-Pin THD, RoHS, Bulk")
      (fields (field (name "MANUFACTURER") "Cherry") (field (name "PART NO") "MX1A11NW"))
      (libsource (lib "mx1a-11nw") (part "CMP-2000-06786-1"))
    )
    (comp (ref "SW32")
      (value "MX1A-11NW")
      (footprint "CHRY-MX1A-11NW_V")
      (description "Keylock Switch, 12 V, -10 to 70 degC, 2-Pin THD, RoHS, Bulk")
      (fields (field (name "MANUFACTURER") "Cherry") (field (name "PART NO") "MX1A11NW"))
      (libsource (lib "mx1a-11nw") (part "CMP-2000-06786-1"))
    )
    (comp (ref "SW33")
      (value "MX1A-11NW")
      (footprint "CHRY-MX1A-11NW_V")
      (description "Keylock Switch, 12 V, -10 to 70 degC, 2-Pin THD, RoHS, Bulk")
      (fields (field (name "MANUFACTURER") "Cherry") (field (name "PART NO") "MX1A11NW"))
      (libsource (lib "mx1a-11nw") (part "CMP-2000-06786-1"))
    )
    (comp (ref "SW34")
      (value "MX1A-11NW")
      (footprint "CHRY-MX1A-11NW_V")
      (description "Keylock Switch, 12 V, -10 to 70 degC, 2-Pin THD, RoHS, Bulk")
      (fields (field (name "MANUFACTURER") "Cherry") (field (name "PART NO") "MX1A11NW"))
      (libsource (lib "mx1a-11nw") (part "CMP-2000-06786-1"))
    )
    (comp (ref "SW35")
      (value "MX1A-11NW")
      (footprint "CHRY-MX1A-11NW_V")
      (description "Keylock Switch, 12 V, -10 to 70 degC, 2-Pin THD, RoHS, Bulk")
      (fields (field (name "MANUFACTURER") "Cherry") (field (name "PART NO") "MX1A11NW"))
      (libsource (lib "mx1a-11nw") (part "CMP-2000-06786-1"))
    )
    (comp (ref "SW36")
      (value "MX1A-11NW")
      (footprint "CHRY-MX1A-11NW_V")
      (description "Keylock Switch, 12 V, -10 to 70 degC, 2-Pin THD, RoHS, Bulk")
      (fields (field (name "MANUFACTURER") "Cherry") (field (name "PART NO") "MX1A11NW"))
      (libsource (lib "mx1a-11nw") (part "CMP-2000-06786-1"))
    )
    (comp (ref "SW37")
      (value "MX1A-11NW")
      (footprint "CHRY-MX1A-11NW_V")
      (description "Keylock Switch, 12 V, -10 to 70 degC, 2-Pin THD, RoHS, Bulk")
      (fields (field (name "MANUFACTURER") "Cherry") (field (name "PART NO") "MX1A11NW"))
      (libsource (lib "mx1a-11nw") (part "CMP-2000-06786-1"))
    )
    (comp (ref "SW38")
      (value "MX1A-11NW")
      (footprint "CHRY-MX1A-11NW_V")
      (description "Keylock Switch, 12 V, -10 to 70 degC, 2-Pin THD, RoHS, Bulk")
      (fields (field (name "MANUFACTURER") "Cherry") (field (name "PART NO") "MX1A11NW"))
      (libsource (lib "mx1a-11nw") (part "CMP-2000-06786-1"))
    )
    (comp (ref "SW39")
      (value "MX1A-11NW")
      (footprint "CHRY-MX1A-11NW_V")
      (description "Keylock Switch, 12 V, -10 to 70 degC, 2-Pin THD, RoHS, Bulk")
      (fields (field (name "MANUFACTURER") "Cherry") (field (name "PART NO") "MX1A11NW"))
      (libsource (lib "mx1a-11nw") (part "CMP-2000-06786-1"))
    )
    (comp (ref "SW40")
      (value "MX1A-11NW")
      (footprint "CHRY-MX1A-11NW_V")
      (description "Keylock Switch, 12 V, -10 to 70 degC, 2-Pin THD, RoHS, Bulk")
      (fields (field (name "MANUFACTURER") "Cherry") (field (name "PART NO") "MX1A11NW"))
      (libsource (lib "mx1a-11nw") (part "CMP-2000-06786-1"))
    )
    (comp (ref "SW41")
      (value "MX1A-11NW")
      (footprint "CHRY-MX1A-11NW_V")
      (description "Keylock Switch, 12 V, -10 to 70 degC, 2-Pin THD, RoHS, Bulk")
      (fields (field (name "MANUFACTURER") "Cherry") (field (name "PART NO") "MX1A11NW"))
      (libsource (lib "mx1a-11nw") (part "CMP-2000-06786-1"))
    )
    (comp (ref "SW42")
      (value "MX1A-11NW")
      (footprint "CHRY-MX1A-11NW_V")
      (description "Keylock Switch, 12 V, -10 to 70 degC, 2-Pin THD, RoHS, Bulk")
      (fields (field (name "MANUFACTURER") "Cherry") (field (name "PART NO") "MX1A11NW"))
      (libsource (lib "mx1a-11nw") (part "CMP-2000-06786-1"))
    )
    (comp (ref "SW43")
      (value "MX1A-11NW")
      (footprint "CHRY-MX1A-11NW_V")
      (description "Keylock Switch, 12 V, -10 to 70 degC, 2-Pin THD, RoHS, Bulk")
      (fields (field (name "MANUFACTURER") "Cherry") (field (name "PART NO") "MX1A11NW"))
      (libsource (lib "mx1a-11nw") (part "CMP-2000-06786-1"))
    )
    (comp (ref "SW44")
      (value "MX1A-11NW")
      (footprint "CHRY-MX1A-11NW_V")
      (description "Keylock Switch, 12 V, -10 to 70 degC, 2-Pin THD, RoHS, Bulk")
      (fields (field (name "MANUFACTURER") "Cherry") (field (name "PART NO") "MX1A11NW"))
      (libsource (lib "mx1a-11nw") (part "CMP-2000-06786-1"))
    )
    (comp (ref "SW45")
      (value "MX1A-11NW")
      (footprint "CHRY-MX1A-11NW_V")
      (description "Keylock Switch, 12 V, -10 to 70 degC, 2-Pin THD, RoHS, Bulk")
      (fields (field (name "MANUFACTURER") "Cherry") (field (name "PART NO") "MX1A11NW"))
      (libsource (lib "mx1a-11nw") (part "CMP-2000-06786-1"))
    )
    (comp (ref "SW46")
      (value "MX1A-11NW")
      (footprint "CHRY-MX1A-11NW_V")
      (description "Keylock Switch, 12 V, -10 to 70 degC, 2-Pin THD, RoHS, Bulk")
      (fields (field (name "MANUFACTURER") "Cherry") (field (name "PART NO") "MX1A11NW"))
      (libsource (lib "mx1a-11nw") (part "CMP-2000-06786-1"))
    )
    (comp (ref "SW47")
      (value "MX1A-11NW")
      (footprint "CHRY-MX1A-11NW_V")
      (description "Keylock Switch, 12 V, -10 to 70 degC, 2-Pin THD, RoHS, Bulk")
      (fields (field (name "MANUFACTURER") "Cherry") (field (name "PART NO") "MX1A11NW"))
      (libsource (lib "mx1a-11nw") (part "CMP-2000-06786-1"))
    )
    (comp (ref "SW48")
      (value "MX1A-11NW")
      (footprint "CHRY-MX1A-11NW_V")
      (description "Keylock Switch, 12 V, -10 to 70 degC, 2-Pin THD, RoHS, Bulk")
      (fields (field (name "MANUFACTURER") "Cherry") (field (name "PART NO") "MX1A11NW"))
      (libsource (lib "mx1a-11nw") (part "CMP-2000-06786-1"))
    )
    (comp (ref "SW49")
      (value "MX1A-11NW")
      (footprint "CHRY-MX1A-11NW_V")
      (description "Keylock Switch, 12 V, -10 to 70 degC, 2-Pin THD, RoHS, Bulk")
      (fields (field (name "MANUFACTURER") "Cherry") (field (name "PART NO") "MX1A11NW"))
      (libsource (lib "mx1a-11nw") (part "CMP-2000-06786-1"))
    )
    (comp (ref "SW50")
      (value "MX1A-11NW")
      (footprint "CHRY-MX1A-11NW_V")
      (description "Keylock Switch, 12 V, -10 to 70 degC, 2-Pin THD, RoHS, Bulk")
      (fields (field (name "MANUFACTURER") "Cherry") (field (name "PART NO") "MX1A11NW"))
      (libsource (lib "mx1a-11nw") (part "CMP-2000-06786-1"))
    )
    (comp (ref "SW51")
      (value "MX1A-11NW")
      (footprint "CHRY-MX1A-11NW_V")
      (description "Keylock Switch, 12 V, -10 to 70 degC, 2-Pin THD, RoHS, Bulk")
      (fields (field (name "MANUFACTURER") "Cherry") (field (name "PART NO") "MX1A11NW"))
      (libsource (lib "mx1a-11nw") (part "CMP-2000-06786-1"))
    )
    (comp (ref "SW52")
      (value "MX1A-11NW")
      (footprint "CHRY-MX1A-11NW_V")
      (description "Keylock Switch, 12 V, -10 to 70 degC, 2-Pin THD, RoHS, Bulk")
      (fields (field (name "MANUFACTURER") "Cherry") (field (name "PART NO") "MX1A11NW"))
      (libsource (lib "mx1a-11nw") (part "CMP-2000-06786-1"))
    )
    (comp (ref "SW53")
      (value "MX1A-11NW")
      (footprint "CHRY-MX1A-11NW_V")
      (description "Keylock Switch, 12 V, -10 to 70 degC, 2-Pin THD, RoHS, Bulk")
      (fields (field (name "MANUFACTURER") "Cherry") (field (name "PART NO") "MX1A11NW"))
      (libsource (lib "mx1a-11nw") (part "CMP-2000-06786-1"))
    )
    (comp (ref "SW54")
      (value "MX1A-11NW")
      (footprint "CHRY-MX1A-11NW_V")
      (description "Keylock Switch, 12 V, -10 to 70 degC, 2-Pin THD, RoHS, Bulk")
      (fields (field (name "MANUFACTURER") "Cherry") (field (name "PART NO") "MX1A11NW"))
      (libsource (lib "mx1a-11nw") (part "CMP-2000-06786-1"))
    )
    (comp (ref "SW55")
      (value "MX1A-11NW")
      (footprint "CHRY-MX1A-11NW_V")
      (description "Keylock Switch, 12 V, -10 to 70 degC, 2-Pin THD, RoHS, Bulk")
      (fields (field (name "MANUFACTURER") "Cherry") (field (name "PART NO") "MX1A11NW"))
      (libsource (lib "mx1a-11nw") (part "CMP-2000-06786-1"))
    )
    (comp (ref "SW56")
      (value "MX1A-11NW")
      (footprint "CHRY-MX1A-11NW_V")
      (description "Keylock Switch, 12 V, -10 to 70 degC, 2-Pin THD, RoHS, Bulk")
      (fields (field (name "MANUFACTURER") "Cherry") (field (name "PART NO") "MX1A11NW"))
      (libsource (lib "mx1a-11nw") (part "CMP-2000-06786-1"))
    )
    (comp (ref "SW57")
      (value "MX1A-11NW")
      (footprint "CHRY-MX1A-11NW_V")
      (description "Keylock Switch, 12 V, -10 to 70 degC, 2-Pin THD, RoHS, Bulk")
      (fields (field (name "MANUFACTURER") "Cherry") (field (name "PART NO") "MX1A11NW"))
      (libsource (lib "mx1a-11nw") (part "CMP-2000-06786-1"))
    )
    (comp (ref "SW58")
      (value "MX1A-11NW")
      (footprint "CHRY-MX1A-11NW_V")
      (description "Keylock Switch, 12 V, -10 to 70 degC, 2-Pin THD, RoHS, Bulk")
      (fields (field (name "MANUFACTURER") "Cherry") (field (name "PART NO") "MX1A11NW"))
      (libsource (lib "mx1a-11nw") (part "CMP-2000-06786-1"))
    )
    (comp (ref "SW59")
      (value "MX1A-11NW")
      (footprint "CHRY-MX1A-11NW_V")
      (description "Keylock Switch, 12 V, -10 to 70 degC, 2-Pin THD, RoHS, Bulk")
      (fields (field (name "MANUFACTURER") "Cherry") (field (name "PART NO") "MX1A11NW"))
      (libsource (lib "mx1a-11nw") (part "CMP-2000-06786-1"))
    )
    (comp (ref "SW60")
      (value "MX1A-11NW")
      (footprint "CHRY-MX1A-11NW_V")
      (description "Keylock Switch, 12 V, -10 to 70 degC, 2-Pin THD, RoHS, Bulk")
      (fields (field (name "MANUFACTURER") "Cherry") (field (name "PART NO") "MX1A11NW"))
      (libsource (lib "mx1a-11nw") (part "CMP-2000-06786-1"))
    )
    (comp (ref "SW61")
      (value "MX1A-11NW")
      (footprint "CHRY-MX1A-11NW_V")
      (description "Keylock Switch, 12 V, -10 to 70 degC, 2-Pin THD, RoHS, Bulk")
      (fields (field (name "MANUFACTURER") "Cherry") (field (name "PART NO") "MX1A11NW"))
      (libsource (lib "mx1a-11nw") (part "CMP-2000-06786-1"))
    )
    (comp (ref "SW62")
      (value "MX1A-11NW")
      (footprint "CHRY-MX1A-11NW_V")
      (description "Keylock Switch, 12 V, -10 to 70 degC, 2-Pin THD, RoHS, Bulk")
      (fields (field (name "MANUFACTURER") "Cherry") (field (name "PART NO") "MX1A11NW"))
      (libsource (lib "mx1a-11nw") (part "CMP-2000-06786-1"))
    )
    (comp (ref "SW63")
      (value "MX1A-11NW")
      (footprint "CHRY-MX1A-11NW_V")
      (description "Keylock Switch, 12 V, -10 to 70 degC, 2-Pin THD, RoHS, Bulk")
      (fields (field (name "MANUFACTURER") "Cherry") (field (name "PART NO") "MX1A11NW"))
      (libsource (lib "mx1a-11nw") (part "CMP-2000-06786-1"))
    )
    (comp (ref "SW64")
      (value "MX1A-11NW")
      (footprint "CHRY-MX1A-11NW_V")
      (description "Keylock Switch, 12 V, -10 to 70 degC, 2-Pin THD, RoHS, Bulk")
      (fields (field (name "MANUFACTURER") "Cherry") (field (name "PART NO") "MX1A11NW"))
      (libsource (lib "mx1a-11nw") (part "CMP-2000-06786-1"))
    )
    (comp (ref "SW65")
      (value "MX1A-11NW")
      (footprint "CHRY-MX1A-11NW_V")
      (description "Keylock Switch, 12 V, -10 to 70 degC, 2-Pin THD, RoHS, Bulk")
      (fields (field (name "MANUFACTURER") "Cherry") (field (name "PART NO") "MX1A11NW"))
      (libsource (lib "mx1a-11nw") (part "CMP-2000-06786-1"))
    )
    (comp (ref "SW66")
      (value "MX1A-11NW")
      (footprint "CHRY-MX1A-11NW_V")
      (description "Keylock Switch, 12 V, -10 to 70 degC, 2-Pin THD, RoHS, Bulk")
      (fields (field (name "MANUFACTURER") "Cherry") (field (name "PART NO") "MX1A11NW"))
      (libsource (lib "mx1a-11nw") (part "CMP-2000-06786-1"))
    )
    (comp (ref "SW67")
      (value "MX1A-11NW")
      (footprint "CHRY-MX1A-11NW_V")
      (description "Keylock Switch, 12 V, -10 to 70 degC, 2-Pin THD, RoHS, Bulk")
      (fields (field (name "MANUFACTURER") "Cherry") (field (name "PART NO") "MX1A11NW"))
      (libsource (lib "mx1a-11nw") (part "CMP-2000-06786-1"))
    )
    (comp (ref "SW68")
      (value "MX1A-11NW")
      (footprint "CHRY-MX1A-11NW_V")
      (description "Keylock Switch, 12 V, -10 to 70 degC, 2-Pin THD, RoHS, Bulk")
      (fields (field (name "MANUFACTURER") "Cherry") (field (name "PART NO") "MX1A11NW"))
      (libsource (lib "mx1a-11nw") (part "CMP-2000-06786-1"))
    )
    (comp (ref "SW69")
      (value "MX1A-11NW")
      (footprint "CHRY-MX1A-11NW_V")
      (description "Keylock Switch, 12 V, -10 to 70 degC, 2-Pin THD, RoHS, Bulk")
      (fields (field (name "MANUFACTURER") "Cherry") (field (name "PART NO") "MX1A11NW"))
      (libsource (lib "mx1a-11nw") (part "CMP-2000-06786-1"))
    )
    (comp (ref "SW70")
      (value "MX1A-11NW")
      (footprint "CHRY-MX1A-11NW_V")
      (description "Keylock Switch, 12 V, -10 to 70 degC, 2-Pin THD, RoHS, Bulk")
      (fields (field (name "MANUFACTURER") "Cherry") (field (name "PART NO") "MX1A11NW"))
      (libsource (lib "mx1a-11nw") (part "CMP-2000-06786-1"))
    )
    (comp (ref "SW71")
      (value "MX1A-11NW")
      (footprint "CHRY-MX1A-11NW_V")
      (description "Keylock Switch, 12 V, -10 to 70 degC, 2-Pin THD, RoHS, Bulk")
      (fields (field (name "MANUFACTURER") "Cherry") (field (name "PART NO") "MX1A11NW"))
      (libsource (lib "mx1a-11nw") (part "CMP-2000-06786-1"))
    )
    (comp (ref "SW72")
      (value "MX1A-11NW")
      (footprint "CHRY-MX1A-11NW_V")
      (description "Keylock Switch, 12 V, -10 to 70 degC, 2-Pin THD, RoHS, Bulk")
      (fields (field (name "MANUFACTURER") "Cherry") (field (name "PART NO") "MX1A11NW"))
      (libsource (lib "mx1a-11nw") (part "CMP-2000-06786-1"))
    )
    (comp (ref "SW73")
      (value "MX1A-11NW")
      (footprint "CHRY-MX1A-11NW_V")
      (description "Keylock Switch, 12 V, -10 to 70 degC, 2-Pin THD, RoHS, Bulk")
      (fields (field (name "MANUFACTURER") "Cherry") (field (name "PART NO") "MX1A11NW"))
      (libsource (lib "mx1a-11nw") (part "CMP-2000-06786-1"))
    )
    (comp (ref "SW74")
      (value "MX1A-11NW")
      (footprint "CHRY-MX1A-11NW_V")
      (description "Keylock Switch, 12 V, -10 to 70 degC, 2-Pin THD, RoHS, Bulk")
      (fields (field (name "MANUFACTURER") "Cherry") (field (name "PART NO") "MX1A11NW"))
      (libsource (lib "mx1a-11nw") (part "CMP-2000-06786-1"))
    )
    (comp (ref "SW75")
      (value "MX1A-11NW")
      (footprint "CHRY-MX1A-11NW_V")
      (description "Keylock Switch, 12 V, -10 to 70 degC, 2-Pin THD, RoHS, Bulk")
      (fields (field (name "MANUFACTURER") "Cherry") (field (name "PART NO") "MX1A11NW"))
      (libsource (lib "mx1a-11nw") (part "CMP-2000-06786-1"))
    )
    (comp (ref "SW76")
      (value "MX1A-11NW")
      (footprint "CHRY-MX1A-11NW_V")
      (description "Keylock Switch, 12 V, -10 to 70 degC, 2-Pin THD, RoHS, Bulk")
      (fields (field (name "MANUFACTURER") "Cherry") (field (name "PART NO") "MX1A11NW"))
      (libsource (lib "mx1a-11nw") (part "CMP-2000-06786-1"))
    )
    (comp (ref "SW77")
      (value "MX1A-11NW")
      (footprint "CHRY-MX1A-11NW_V")
      (description "Keylock Switch, 12 V, -10 to 70 degC, 2-Pin THD, RoHS, Bulk")
      (fields (field (name "MANUFACTURER") "Cherry") (field (name "PART NO") "MX1A11NW"))
      (libsource (lib "mx1a-11nw") (part "CMP-2000-06786-1"))
    )
    (comp (ref "SW78")
      (value "MX1A-11NW")
      (footprint "CHRY-MX1A-11NW_V")
      (description "Keylock Switch, 12 V, -10 to 70 degC, 2-Pin THD, RoHS, Bulk")
      (fields (field (name "MANUFACTURER") "Cherry") (field (name "PART NO") "MX1A11NW"))
      (libsource (lib "mx1a-11nw") (part "CMP-2000-06786-1"))
    )
    (comp (ref "SW79")
      (value "MX1A-11NW")
      (footprint "CHRY-MX1A-11NW_V")
      (description "Keylock Switch, 12 V, -10 to 70 degC, 2-Pin THD, RoHS, Bulk")
      (fields (field (name "MANUFACTURER") "Cherry") (field (name "PART NO") "MX1A11NW"))
      (libsource (lib "mx1a-11nw") (part "CMP-2000-06786-1"))
    )
    (comp (ref "SW80")
      (value "MX1A-11NW")
      (footprint "CHRY-MX1A-11NW_V")
      (description "Keylock Switch, 12 V, -10 to 70 degC, 2-Pin THD, RoHS, Bulk")
      (fields (field (name "MANUFACTURER") "Cherry") (field (name "PART NO") "MX1A11NW"))
      (libsource (lib "mx1a-11nw") (part "CMP-2000-06786-1"))
    )
    (comp (ref "SW81")
      (value "MX1A-11NW")
      (footprint "CHRY-MX1A-11NW_V")
      (description "Keylock Switch, 12 V, -10 to 70 degC, 2-Pin THD, RoHS, Bulk")
      (fields (field (name "MANUFACTURER") "Cherry") (field (name "PART NO") "MX1A11NW"))
      (libsource (lib "mx1a-11nw") (part "CMP-2000-06786-1"))
    )
    (comp (ref "SW82")
      (value "MX1A-11NW")
      (footprint "CHRY-MX1A-11NW_V")
      (description "Keylock Switch, 12 V, -10 to 70 degC, 2-Pin THD, RoHS, Bulk")
      (fields (field (name "MANUFACTURER") "Cherry") (field (name "PART NO") "MX1A11NW"))
      (libsource (lib "mx1a-11nw") (part "CMP-2000-06786-1"))
    )
    (comp (ref "SW83")
      (value "MX1A-11NW")
      (footprint "CHRY-MX1A-11NW_V")
      (description "Keylock Switch, 12 V, -10 to 70 degC, 2-Pin THD, RoHS, Bulk")
      (fields (field (name "MANUFACTURER") "Cherry") (field (name "PART NO") "MX1A11NW"))
      (libsource (lib "mx1a-11nw") (part "CMP-2000-06786-1"))
    )
    (comp (ref "SW84")
      (value "MX1A-11NW")
      (footprint "CHRY-MX1A-11NW_V")
      (description "Keylock Switch, 12 V, -10 to 70 degC, 2-Pin THD, RoHS, Bulk")
      (fields (field (name "MANUFACTURER") "Cherry") (field (name "PART NO") "MX1A11NW"))
      (libsource (lib "mx1a-11nw") (part "CMP-2000-06786-1"))
    )
    (comp (ref "SW85")
      (value "MX1A-11NW")
      (footprint "CHRY-MX1A-11NW_V")
      (description "Keylock Switch, 12 V, -10 to 70 degC, 2-Pin THD, RoHS, Bulk")
      (fields (field (name "MANUFACTURER") "Cherry") (field (name "PART NO") "MX1A11NW"))
      (libsource (lib "mx1a-11nw") (part "CMP-2000-06786-1"))
    )
    (comp (ref "SW86")
      (value "MX1A-11NW")
      (footprint "CHRY-MX1A-11NW_V")
      (description "Keylock Switch, 12 V, -10 to 70 degC, 2-Pin THD, RoHS, Bulk")
      (fields (field (name "MANUFACTURER") "Cherry") (field (name "PART NO") "MX1A11NW"))
      (libsource (lib "mx1a-11nw") (part "CMP-2000-06786-1"))
    )
    (comp (ref "SW87")
      (value "MX1A-11NW")
      (footprint "CHRY-MX1A-11NW_V")
      (description "Keylock Switch, 12 V, -10 to 70 degC, 2-Pin THD, RoHS, Bulk")
      (fields (field (name "MANUFACTURER") "Cherry") (field (name "PART NO") "MX1A11NW"))
      (libsource (lib "mx1a-11nw") (part "CMP-2000-06786-1"))
    )
    (comp (ref "SW88")
      (value "MX1A-11NW")
      (footprint "CHRY-MX1A-11NW_V")
      (description "Keylock Switch, 12 V, -10 to 70 degC, 2-Pin THD, RoHS, Bulk")
      (fields (field (name "MANUFACTURER") "Cherry") (field (name "PART NO") "MX1A11NW"))
      (libsource (lib "mx1a-11nw") (part "CMP-2000-06786-1"))
    )
    (comp (ref "SW89")
      (value "MX1A-11NW")
      (footprint "CHRY-MX1A-11NW_V")
      (description "Keylock Switch, 12 V, -10 to 70 degC, 2-Pin THD, RoHS, Bulk")
      (fields (field (name "MANUFACTURER") "Cherry") (field (name "PART NO") "MX1A11NW"))
      (libsource (lib "mx1a-11nw") (part "CMP-2000-06786-1"))
    )
    (comp (ref "SW90")
      (value "MX1A-11NW")
      (footprint "CHRY-MX1A-11NW_V")
      (description "Keylock Switch, 12 V, -10 to 70 degC, 2-Pin THD, RoHS, Bulk")
      (fields (field (name "MANUFACTURER") "Cherry") (field (name "PART NO") "MX1A11NW"))
      (libsource (lib "mx1a-11nw") (part "CMP-2000-06786-1"))
    )
    (comp (ref "SW91")
      (value "MX1A-11NW")
      (footprint "CHRY-MX1A-11NW_V")
      (description "Keylock Switch, 12 V, -10 to 70 degC, 2-Pin THD, RoHS, Bulk")
      (fields (field (name "MANUFACTURER") "Cherry") (field (name "PART NO") "MX1A11NW"))
      (libsource (lib "mx1a-11nw") (part "CMP-2000-06786-1"))
    )
    (comp (ref "SW92")
      (value "MX1A-11NW")
      (footprint "CHRY-MX1A-11NW_V")
      (description "Keylock Switch, 12 V, -10 to 70 degC, 2-Pin THD, RoHS, Bulk")
      (fields (field (name "MANUFACTURER") "Cherry") (field (name "PART NO") "MX1A11NW"))
      (libsource (lib "mx1a-11nw") (part "CMP-2000-06786-1"))
    )
    (comp (ref "SW93")
      (value "MX1A-11NW")
      (footprint "CHRY-MX1A-11NW_V")
      (description "Keylock Switch, 12 V, -10 to 70 degC, 2-Pin THD, RoHS, Bulk")
      (fields (field (name "MANUFACTURER") "Cherry") (field (name "PART NO") "MX1A11NW"))
      (libsource (lib "mx1a-11nw") (part "CMP-2000-06786-1"))
    )
    (comp (ref "SW94")
      (value "MX1A-11NW")
      (footprint "CHRY-MX1A-11NW_V")
      (description "Keylock Switch, 12 V, -10 to 70 degC, 2-Pin THD, RoHS, Bulk")
      (fields (field (name "MANUFACTURER") "Cherry") (field (name "PART NO") "MX1A11NW"))
      (libsource (lib "mx1a-11nw") (part "CMP-2000-06786-1"))
    )
    (comp (ref "SW95")
      (value "MX1A-11NW")
      (footprint "CHRY-MX1A-11NW_V")
      (description "Keylock Switch, 12 V, -10 to 70 degC, 2-Pin THD, RoHS, Bulk")
      (fields (field (name "MANUFACTURER") "Cherry") (field (name "PART NO") "MX1A11NW"))
      (libsource (lib "mx1a-11nw") (part "CMP-2000-06786-1"))
    )
    (comp (ref "SW96")
      (value "MX1A-11NW")
      (footprint "CHRY-MX1A-11NW_V")
      (description "Keylock Switch, 12 V, -10 to 70 degC, 2-Pin THD, RoHS, Bulk")
      (fields (field (name "MANUFACTURER") "Cherry") (field (name "PART NO") "MX1A11NW"))
      (libsource (lib "mx1a-11nw") (part "CMP-2000-06786-1"))
    )
    (comp (ref "SW97")
      (value "MX1A-11NW")
      (footprint "CHRY-MX1A-11NW_V")
      (description "Keylock Switch, 12 V, -10 to 70 degC, 2-Pin THD, RoHS, Bulk")
      (fields (field (name "MANUFACTURER") "Cherry") (field (name "PART NO") "MX1A11NW"))
      (libsource (lib "mx1a-11nw") (part "CMP-2000-06786-1"))
    )
    (comp (ref "SW98")
      (value "MX1A-11NW")
      (footprint "CHRY-MX1A-11NW_V")
      (description "Keylock Switch, 12 V, -10 to 70 degC, 2-Pin THD, RoHS, Bulk")
      (fields (field (name "MANUFACTURER") "Cherry") (field (name "PART NO") "MX1A11NW"))
      (libsource (lib "mx1a-11nw") (part "CMP-2000-06786-1"))
    )
    (comp (ref "SW99")
      (value "MX1A-11NW")
      (footprint "CHRY-MX1A-11NW_V")
      (description "Keylock Switch, 12 V, -10 to 70 degC, 2-Pin THD, RoHS, Bulk")
      (fields (field (name "MANUFACTURER") "Cherry") (field (name "PART NO") "MX1A11NW"))
      (libsource (lib "mx1a-11nw") (part "CMP-2000-06786-1"))
    )
    (comp (ref "SW100")
      (value "MX1A-11NW")
      (footprint "CHRY-MX1A-11NW_V")
      (description "Keylock Switch, 12 V, -10 to 70 degC, 2-Pin THD, RoHS, Bulk")
      (fields (field (name "MANUFACTURER") "Cherry") (field (name "PART NO") "MX1A11NW"))
      (libsource (lib "mx1a-11nw") (part "CMP-2000-06786-1"))
    )
    (comp (ref "SW101")
      (value "MX1A-11NW")
      (footprint "CHRY-MX1A-11NW_V")
      (description "Keylock Switch, 12 V, -10 to 70 degC, 2-Pin THD, RoHS, Bulk")
      (fields (field (name "MANUFACTURER") "Cherry") (field (name "PART NO") "MX1A11NW"))
      (libsource (lib "mx1a-11nw") (part "CMP-2000-06786-1"))
    )
    (comp (ref "SW102")
      (value "MX1A-11NW")
      (footprint "CHRY-MX1A-11NW_V")
      (description "Keylock Switch, 12 V, -10 to 70 degC, 2-Pin THD, RoHS, Bulk")
      (fields (field (name "MANUFACTURER") "Cherry") (field (name "PART NO") "MX1A11NW"))
      (libsource (lib "mx1a-11nw") (part "CMP-2000-06786-1"))
    )
    (comp (ref "SW103")
      (value "MX1A-11NW")
      (footprint "CHRY-MX1A-11NW_V")
      (description "Keylock Switch, 12 V, -10 to 70 degC, 2-Pin THD, RoHS, Bulk")
      (fields (field (name "MANUFACTURER") "Cherry") (field (name "PART NO") "MX1A11NW"))
      (libsource (lib "mx1a-11nw") (part "CMP-2000-06786-1"))
    )
    (comp (ref "SW104")
      (value "MX1A-11NW")
      (footprint "CHRY-MX1A-11NW_V")
      (description "Keylock Switch, 12 V, -10 to 70 degC, 2-Pin THD, RoHS, Bulk")
      (fields (field (name "MANUFACTURER") "Cherry") (field (name "PART NO") "MX1A11NW"))
      (libsource (lib "mx1a-11nw") (part "CMP-2000-06786-1"))
    )
    (comp (ref "SW105")
      (value "MX1A-11NW")
      (footprint "CHRY-MX1A-11NW_V")
      (description "Keylock Switch, 12 V, -10 to 70 degC, 2-Pin THD, RoHS, Bulk")
      (fields (field (name "MANUFACTURER") "Cherry") (field (name "PART NO") "MX1A11NW"))
      (libsource (lib "mx1a-11nw") (part "CMP-2000-06786-1"))
    )
    (comp (ref "SW106")
      (value "MX1A-11NW")
      (footprint "CHRY-MX1A-11NW_V")
      (description "Keylock Switch, 12 V, -10 to 70 degC, 2-Pin THD, RoHS, Bulk")
      (fields (field (name "MANUFACTURER") "Cherry") (field (name "PART NO") "MX1A11NW"))
      (libsource (lib "mx1a-11nw") (part "CMP-2000-06786-1"))
    )
    (comp (ref "SW107")
      (value "MX1A-11NW")
      (footprint "CHRY-MX1A-11NW_V")
      (description "Keylock Switch, 12 V, -10 to 70 degC, 2-Pin THD, RoHS, Bulk")
      (fields (field (name "MANUFACTURER") "Cherry") (field (name "PART NO") "MX1A11NW"))
      (libsource (lib "mx1a-11nw") (part "CMP-2000-06786-1"))
    )
    (comp (ref "SW108")
      (value "MX1A-11NW")
      (footprint "CHRY-MX1A-11NW_V")
      (description "Keylock Switch, 12 V, -10 to 70 degC, 2-Pin THD, RoHS, Bulk")
      (fields (field (name "MANUFACTURER") "Cherry") (field (name "PART NO") "MX1A11NW"))
      (libsource (lib "mx1a-11nw") (part "CMP-2000-06786-1"))
    )
    (comp (ref "SW109")
      (value "MX1A-11NW")
      (footprint "CHRY-MX1A-11NW_V")
      (description "Keylock Switch, 12 V, -10 to 70 degC, 2-Pin THD, RoHS, Bulk")
      (fields (field (name "MANUFACTURER") "Cherry") (field (name "PART NO") "MX1A11NW"))
      (libsource (lib "mx1a-11nw") (part "CMP-2000-06786-1"))
    )
    (comp (ref "SW110")
      (value "MX1A-11NW")
      (footprint "CHRY-MX1A-11NW_V")
      (description "Keylock Switch, 12 V, -10 to 70 degC, 2-Pin THD, RoHS, Bulk")
      (fields (field (name "MANUFACTURER") "Cherry") (field (name "PART NO") "MX1A11NW"))
      (libsource (lib "mx1a-11nw") (part "CMP-2000-06786-1"))
    )
    (comp (ref "SW111")
      (value "MX1A-11NW")
      (footprint "CHRY-MX1A-11NW_V")
      (description "Keylock Switch, 12 V, -10 to 70 degC, 2-Pin THD, RoHS, Bulk")
      (fields (field (name "MANUFACTURER") "Cherry") (field (name "PART NO") "MX1A11NW"))
      (libsource (lib "mx1a-11nw") (part "CMP-2000-06786-1"))
    )
    (comp (ref "SW112")
      (value "MX1A-11NW")
      (footprint "CHRY-MX1A-11NW_V")
      (description "Keylock Switch, 12 V, -10 to 70 degC, 2-Pin THD, RoHS, Bulk")
      (fields (field (name "MANUFACTURER") "Cherry") (field (name "PART NO") "MX1A11NW"))
      (libsource (lib "mx1a-11nw") (part "CMP-2000-06786-1"))
    )
    (comp (ref "SW113")
      (value "MX1A-11NW")
      (footprint "CHRY-MX1A-11NW_V")
      (description "Keylock Switch, 12 V, -10 to 70 degC, 2-Pin THD, RoHS, Bulk")
      (fields (field (name "MANUFACTURER") "Cherry") (field (name "PART NO") "MX1A11NW"))
      (libsource (lib "mx1a-11nw") (part "CMP-2000-06786-1"))
    )
    (comp (ref "SW114")
      (value "MX1A-11NW")
      (footprint "CHRY-MX1A-11NW_V")
      (description "Keylock Switch, 12 V, -10 to 70 degC, 2-Pin THD, RoHS, Bulk")
      (fields (field (name "MANUFACTURER") "Cherry") (field (name "PART NO") "MX1A11NW"))
      (libsource (lib "mx1a-11nw") (part "CMP-2000-06786-1"))
    )
    (comp (ref "SW115")
      (value "MX1A-11NW")
      (footprint "CHRY-MX1A-11NW_V")
      (description "Keylock Switch, 12 V, -10 to 70 degC, 2-Pin THD, RoHS, Bulk")
      (fields (field (name "MANUFACTURER") "Cherry") (field (name "PART NO") "MX1A11NW"))
      (libsource (lib "mx1a-11nw") (part "CMP-2000-06786-1"))
    )
    (comp (ref "SW116")
      (value "MX1A-11NW")
      (footprint "CHRY-MX1A-11NW_V")
      (description "Keylock Switch, 12 V, -10 to 70 degC, 2-Pin THD, RoHS, Bulk")
      (fields (field (name "MANUFACTURER") "Cherry") (field (name "PART NO") "MX1A11NW"))
      (libsource (lib "mx1a-11nw") (part "CMP-2000-06786-1"))
    )
    (comp (ref "SW117")
      (value "MX1A-11NW")
      (footprint "CHRY-MX1A-11NW_V")
      (description "Keylock Switch, 12 V, -10 to 70 degC, 2-Pin THD, RoHS, Bulk")
      (fields (field (name "MANUFACTURER") "Cherry") (field (name "PART NO") "MX1A11NW"))
      (libsource (lib "mx1a-11nw") (part "CMP-2000-06786-1"))
    )
    (comp (ref "SW118")
      (value "MX1A-11NW")
      (footprint "CHRY-MX1A-11NW_V")
      (description "Keylock Switch, 12 V, -10 to 70 degC, 2-Pin THD, RoHS, Bulk")
      (fields (field (name "MANUFACTURER") "Cherry") (field (name "PART NO") "MX1A11NW"))
      (libsource (lib "mx1a-11nw") (part "CMP-2000-06786-1"))
    )
    (comp (ref "SW119")
      (value "MX1A-11NW")
      (footprint "CHRY-MX1A-11NW_V")
      (description "Keylock Switch, 12 V, -10 to 70 degC, 2-Pin THD, RoHS, Bulk")
      (fields (field (name "MANUFACTURER") "Cherry") (field (name "PART NO") "MX1A11NW"))
      (libsource (lib "mx1a-11nw") (part "CMP-2000-06786-1"))
    )
    (comp (ref "SW120")
      (value "MX1A-11NW")
      (footprint "CHRY-MX1A-11NW_V")
      (description "Keylock Switch, 12 V, -10 to 70 degC, 2-Pin THD, RoHS, Bulk")
      (fields (field (name "MANUFACTURER") "Cherry") (field (name "PART NO") "MX1A11NW"))
      (libsource (lib "mx1a-11nw") (part "CMP-2000-06786-1"))
    )
    (comp (ref "SW121")
      (value "MX1A-11NW")
      (footprint "CHRY-MX1A-11NW_V")
      (description "Keylock Switch, 12 V, -10 to 70 degC, 2-Pin THD, RoHS, Bulk")
      (fields (field (name "MANUFACTURER") "Cherry") (field (name "PART NO") "MX1A11NW"))
      (libsource (lib "mx1a-11nw") (part "CMP-2000-06786-1"))
    )
    (comp (ref "SW122")
      (value "MX1A-11NW")
      (footprint "CHRY-MX1A-11NW_V")
      (description "Keylock Switch, 12 V, -10 to 70 degC, 2-Pin THD, RoHS, Bulk")
      (fields (field (name "MANUFACTURER") "Cherry") (field (name "PART NO") "MX1A11NW"))
      (libsource (lib "mx1a-11nw") (part "CMP-2000-06786-1"))
    )
    (comp (ref "SW123")
      (value "MX1A-11NW")
      (footprint "CHRY-MX1A-11NW_V")
      (description "Keylock Switch, 12 V, -10 to 70 degC, 2-Pin THD, RoHS, Bulk")
      (fields (field (name "MANUFACTURER") "Cherry") (field (name "PART NO") "MX1A11NW"))
      (libsource (lib "mx1a-11nw") (part "CMP-2000-06786-1"))
    )
    (comp (ref "SW124")
      (value "MX1A-11NW")
      (footprint "CHRY-MX1A-11NW_V")
      (description "Keylock Switch, 12 V, -10 to 70 degC, 2-Pin THD, RoHS, Bulk")
      (fields (field (name "MANUFACTURER") "Cherry") (field (name "PART NO") "MX1A11NW"))
      (libsource (lib "mx1a-11nw") (part "CMP-2000-06786-1"))
    )
    (comp (ref "SW125")
      (value "MX1A-11NW")
      (footprint "CHRY-MX1A-11NW_V")
      (description "Keylock Switch, 12 V, -10 to 70 degC, 2-Pin THD, RoHS, Bulk")
      (fields (field (name "MANUFACTURER") "Cherry") (field (name "PART NO") "MX1A11NW"))
      (libsource (lib "mx1a-11nw") (part "CMP-2000-06786-1"))
    )
    (comp (ref "SW126")
      (value "MX1A-11NW")
      (footprint "CHRY-MX1A-11NW_V")
      (description "Keylock Switch, 12 V, -10 to 70 degC, 2-Pin THD, RoHS, Bulk")
      (fields (field (name "MANUFACTURER") "Cherry") (field (name "PART NO") "MX1A11NW"))
      (libsource (lib "mx1a-11nw") (part "CMP-2000-06786-1"))
    )
  )
  (nets
    (net (code "1") (name "/Column0") (class "Default")
      (node (ref "SW1") (pin "2") (pinfunction "2_2") (pintype "passive"))
      (node (ref "SW106") (pin "2") (pinfunction "2_2") (pintype "passive"))
      (node (ref "SW22") (pin "2") (pinfunction "2_2") (pintype "passive"))
      (node (ref "SW43") (pin "2") (pinfunction "2_2") (pintype "passive"))
      (node (ref "SW64") (pin "2") (pinfunction "2_2") (pintype "passive"))
      (node (ref "SW85") (pin "2") (pinfunction "2_2") (pintype "passive"))
    )
    (net (code "2") (name "/Column1") (class "Default")
      (node (ref "SW107") (pin "2") (pinfunction "2_2") (pintype "passive"))
      (node (ref "SW2") (pin "2") (pinfunction "2_2") (pintype "passive"))
      (node (ref "SW23") (pin "2") (pinfunction "2_2") (pintype "passive"))
      (node (ref "SW44") (pin "2") (pinfunction "2_2") (pintype "passive"))
      (node (ref "SW65") (pin "2") (pinfunction "2_2") (pintype "passive"))
      (node (ref "SW86") (pin "2") (pinfunction "2_2") (pintype "passive"))
    )
    (net (code "3") (name "/Column2") (class "Default")
      (node (ref "SW108") (pin "2") (pinfunction "2_2") (pintype "passive"))
      (node (ref "SW24") (pin "2") (pinfunction "2_2") (pintype "passive"))
      (node (ref "SW3") (pin "2") (pinfunction "2_2") (pintype "passive"))
      (node (ref "SW45") (pin "2") (pinfunction "2_2") (pintype "passive"))
      (node (ref "SW66") (pin "2") (pinfunction "2_2") (pintype "passive"))
      (node (ref "SW87") (pin "2") (pinfunction "2_2") (pintype "passive"))
    )
    (net (code "4") (name "/Column3") (class "Default")
      (node (ref "SW109") (pin "2") (pinfunction "2_2") (pintype "passive"))
      (node (ref "SW25") (pin "2") (pinfunction "2_2") (pintype "passive"))
      (node (ref "SW4") (pin "2") (pinfunction "2_2") (pintype "passive"))
      (node (ref "SW46") (pin "2") (pinfunction "2_2") (pintype "passive"))
      (node (ref "SW67") (pin "2") (pinfunction "2_2") (pintype "passive"))
      (node (ref "SW88") (pin "2") (pinfunction "2_2") (pintype "passive"))
    )
    (net (code "5") (name "/Column4") (class "Default")
      (node (ref "SW110") (pin "2") (pinfunction "2_2") (pintype "passive"))
      (node (ref "SW26") (pin "2") (pinfunction "2_2") (pintype "passive"))
      (node (ref "SW47") (pin "2") (pinfunction "2_2") (pintype "passive"))
      (node (ref "SW5") (pin "2") (pinfunction "2_2") (pintype "passive"))
      (node (ref "SW68") (pin "2") (pinfunction "2_2") (pintype "passive"))
      (node (ref "SW89") (pin "2") (pinfunction "2_2") (pintype "passive"))
    )
    (net (code "6") (name "/Column5") (class "Default")
      (node (ref "SW111") (pin "2") (pinfunction "2_2") (pintype "passive"))
      (node (ref "SW27") (pin "2") (pinfunction "2_2") (pintype "passive"))
      (node (ref "SW48") (pin "2") (pinfunction "2_2") (pintype "passive"))
      (node (ref "SW6") (pin "2") (pinfunction "2_2") (pintype "passive"))
      (node (ref "SW69") (pin "2") (pinfunction "2_2") (pintype "passive"))
      (node (ref "SW90") (pin "2") (pinfunction "2_2") (pintype "passive"))
    )
    (net (code "7") (name "/Column6") (class "Default")
      (node (ref "SW112") (pin "2") (pinfunction "2_2") (pintype "passive"))
      (node (ref "SW28") (pin "2") (pinfunction "2_2") (pintype "passive"))
      (node (ref "SW49") (pin "2") (pinfunction "2_2") (pintype "passive"))
      (node (ref "SW7") (pin "2") (pinfunction "2_2") (pintype "passive"))
      (node (ref "SW70") (pin "2") (pinfunction "2_2") (pintype "passive"))
      (node (ref "SW91") (pin "2") (pinfunction "2_2") (pintype "passive"))
    )
    (net (code "8") (name "/Column7") (class "Default")
      (node (ref "SW113") (pin "2") (pinfunction "2_2") (pintype "passive"))
      (node (ref "SW29") (pin "2") (pinfunction "2_2") (pintype "passive"))
      (node (ref "SW50") (pin "2") (pinfunction "2_2") (pintype "passive"))
      (node (ref "SW71") (pin "2") (pinfunction "2_2") (pintype "passive"))
      (node (ref "SW8") (pin "2") (pinfunction "2_2") (pintype "passive"))
      (node (ref "SW92") (pin "2") (pinfunction "2_2") (pintype "passive"))
    )
    (net (code "9") (name "/Column8") (class "Default")
      (node (ref "SW114") (pin "2") (pinfunction "2_2") (pintype "passive"))
      (node (ref "SW30") (pin "2") (pinfunction "2_2") (pintype "passive"))
      (node (ref "SW51") (pin "2") (pinfunction "2_2") (pintype "passive"))
      (node (ref "SW72") (pin "2") (pinfunction "2_2") (pintype "passive"))
      (node (ref "SW9") (pin "2") (pinfunction "2_2") (pintype "passive"))
      (node (ref "SW93") (pin "2") (pinfunction "2_2") (pintype "passive"))
    )
    (net (code "10") (name "/Column9") (class "Default")
      (node (ref "SW10") (pin "2") (pinfunction "2_2") (pintype "passive"))
      (node (ref "SW115") (pin "2") (pinfunction "2_2") (pintype "passive"))
      (node (ref "SW31") (pin "2") (pinfunction "2_2") (pintype "passive"))
      (node (ref "SW52") (pin "2") (pinfunction "2_2") (pintype "passive"))
      (node (ref "SW73") (pin "2") (pinfunction "2_2") (pintype "passive"))
      (node (ref "SW94") (pin "2") (pinfunction "2_2") (pintype "passive"))
    )
    (net (code "11") (name "/Column10") (class "Default")
      (node (ref "SW11") (pin "2") (pinfunction "2_2") (pintype "passive"))
      (node (ref "SW116") (pin "2") (pinfunction "2_2") (pintype "passive"))
      (node (ref "SW32") (pin "2") (pinfunction "2_2") (pintype "passive"))
      (node (ref "SW53") (pin "2") (pinfunction "2_2") (pintype "passive"))
      (node (ref "SW74") (pin "2") (pinfunction "2_2") (pintype "passive"))
      (node (ref "SW95") (pin "2") (pinfunction "2_2") (pintype "passive"))
    )
    (net (code "12") (name "/Column11") (class "Default")
      (node (ref "SW117") (pin "2") (pinfunction "2_2") (pintype "passive"))
      (node (ref "SW12") (pin "2") (pinfunction "2_2") (pintype "passive"))
      (node (ref "SW33") (pin "2") (pinfunction "2_2") (pintype "passive"))
      (node (ref "SW54") (pin "2") (pinfunction "2_2") (pintype "passive"))
      (node (ref "SW75") (pin "2") (pinfunction "2_2") (pintype "passive"))
      (node (ref "SW96") (pin "2") (pinfunction "2_2") (pintype "passive"))
    )
    (net (code "13") (name "/Column12") (class "Default")
      (node (ref "SW118") (pin "2") (pinfunction "2_2") (pintype "passive"))
      (node (ref "SW13") (pin "2") (pinfunction "2_2") (pintype "passive"))
      (node (ref "SW34") (pin "2") (pinfunction "2_2") (pintype "passive"))
      (node (ref "SW55") (pin "2") (pinfunction "2_2") (pintype "passive"))
      (node (ref "SW76") (pin "2") (pinfunction "2_2") (pintype "passive"))
      (node (ref "SW97") (pin "2") (pinfunction "2_2") (pintype "passive"))
    )
    (net (code "14") (name "/Column13") (class "Default")
      (node (ref "SW119") (pin "2") (pinfunction "2_2") (pintype "passive"))
      (node (ref "SW14") (pin "2") (pinfunction "2_2") (pintype "passive"))
      (node (ref "SW35") (pin "2") (pinfunction "2_2") (pintype "passive"))
      (node (ref "SW56") (pin "2") (pinfunction "2_2") (pintype "passive"))
      (node (ref "SW77") (pin "2") (pinfunction "2_2") (pintype "passive"))
      (node (ref "SW98") (pin "2") (pinfunction "2_2") (pintype "passive"))
    )
    (net (code "15") (name "/Column14") (class "Default")
      (node (ref "SW120") (pin "2") (pinfunction "2_2") (pintype "passive"))
      (node (ref "SW15") (pin "2") (pinfunction "2_2") (pintype "passive"))
      (node (ref "SW36") (pin "2") (pinfunction "2_2") (pintype "passive"))
      (node (ref "SW57") (pin "2") (pinfunction "2_2") (pintype "passive"))
      (node (ref "SW78") (pin "2") (pinfunction "2_2") (pintype "passive"))
      (node (ref "SW99") (pin "2") (pinfunction "2_2") (pintype "passive"))
    )
    (net (code "16") (name "/Column15") (class "Default")
      (node (ref "SW100") (pin "2") (pinfunction "2_2") (pintype "passive"))
      (node (ref "SW121") (pin "2") (pinfunction "2_2") (pintype "passive"))
      (node (ref "SW16") (pin "2") (pinfunction "2_2") (pintype "passive"))
      (node (ref "SW37") (pin "2") (pinfunction "2_2") (pintype "passive"))
      (node (ref "SW58") (pin "2") (pinfunction "2_2") (pintype "passive"))
      (node (ref "SW79") (pin "2") (pinfunction "2_2") (pintype "passive"))
    )
    (net (code "17") (name "/Column16") (class "Default")
      (node (ref "SW101") (pin "2") (pinfunction "2_2") (pintype "passive"))
      (node (ref "SW122") (pin "2") (pinfunction "2_2") (pintype "passive"))
      (node (ref "SW17") (pin "2") (pinfunction "2_2") (pintype "passive"))
      (node (ref "SW38") (pin "2") (pinfunction "2_2") (pintype "passive"))
      (node (ref "SW59") (pin "2") (pinfunction "2_2") (pintype "passive"))
      (node (ref "SW80") (pin "2") (pinfunction "2_2") (pintype "passive"))
    )
    (net (code "18") (name "/Column17") (class "Default")
      (node (ref "SW102") (pin "2") (pinfunction "2_2") (pintype "passive"))
      (node (ref "SW123") (pin "2") (pinfunction "2_2") (pintype "passive"))
      (node (ref "SW18") (pin "2") (pinfunction "2_2") (pintype "passive"))
      (node (ref "SW39") (pin "2") (pinfunction "2_2") (pintype "passive"))
      (node (ref "SW60") (pin "2") (pinfunction "2_2") (pintype "passive"))
      (node (ref "SW81") (pin "2") (pinfunction "2_2") (pintype "passive"))
    )
    (net (code "19") (name "/Column18") (class "Default")
      (node (ref "SW103") (pin "2") (pinfunction "2_2") (pintype "passive"))
      (node (ref "SW124") (pin "2") (pinfunction "2_2") (pintype "passive"))
      (node (ref "SW19") (pin "2") (pinfunction "2_2") (pintype "passive"))
      (node (ref "SW40") (pin "2") (pinfunction "2_2") (pintype "passive"))
      (node (ref "SW61") (pin "2") (pinfunction "2_2") (pintype "passive"))
      (node (ref "SW82") (pin "2") (pinfunction "2_2") (pintype "passive"))
    )
    (net (code "20") (name "/Column19") (class "Default")
      (node (ref "SW104") (pin "2") (pinfunction "2_2") (pintype "passive"))
      (node (ref "SW125") (pin "2") (pinfunction "2_2") (pintype "passive"))
      (node (ref "SW20") (pin "2") (pinfunction "2_2") (pintype "passive"))
      (node (ref "SW41") (pin "2") (pinfunction "2_2") (pintype "passive"))
      (node (ref "SW62") (pin "2") (pinfunction "2_2") (pintype "passive"))
      (node (ref "SW83") (pin "2") (pinfunction "2_2") (pintype "passive"))
    )
    (net (code "21") (name "/Column20") (class "Default")
      (node (ref "SW105") (pin "2") (pinfunction "2_2") (pintype "passive"))
      (node (ref "SW126") (pin "2") (pinfunction "2_2") (pintype "passive"))
      (node (ref "SW21") (pin "2") (pinfunction "2_2") (pintype "passive"))
      (node (ref "SW42") (pin "2") (pinfunction "2_2") (pintype "passive"))
      (node (ref "SW63") (pin "2") (pinfunction "2_2") (pintype "passive"))
      (node (ref "SW84") (pin "2") (pinfunction "2_2") (pintype "passive"))
    )
    (net (code "22") (name "/Row0") (class "Default")
      (node (ref "D1") (pin "1") (pinfunction "K_1") (pintype "passive"))
      (node (ref "D10") (pin "1") (pinfunction "K_1") (pintype "passive"))
      (node (ref "D11") (pin "1") (pinfunction "K_1") (pintype "passive"))
      (node (ref "D12") (pin "1") (pinfunction "K_1") (pintype "passive"))
      (node (ref "D13") (pin "1") (pinfunction "K_1") (pintype "passive"))
      (node (ref "D14") (pin "1") (pinfunction "K_1") (pintype "passive"))
      (node (ref "D15") (pin "1") (pinfunction "K_1") (pintype "passive"))
      (node (ref "D16") (pin "1") (pinfunction "K_1") (pintype "passive"))
      (node (ref "D17") (pin "1") (pinfunction "K_1") (pintype "passive"))
      (node (ref "D18") (pin "1") (pinfunction "K_1") (pintype "passive"))
      (node (ref "D19") (pin "1") (pinfunction "K_1") (pintype "passive"))
      (node (ref "D2") (pin "1") (pinfunction "K_1") (pintype "passive"))
      (node (ref "D20") (pin "1") (pinfunction "K_1") (pintype "passive"))
      (node (ref "D21") (pin "1") (pinfunction "K_1") (pintype "passive"))
      (node (ref "D3") (pin "1") (pinfunction "K_1") (pintype "passive"))
      (node (ref "D4") (pin "1") (pinfunction "K_1") (pintype "passive"))
      (node (ref "D5") (pin "1") (pinfunction "K_1") (pintype "passive"))
      (node (ref "D6") (pin "1") (pinfunction "K_1") (pintype "passive"))
      (node (ref "D7") (pin "1") (pinfunction "K_1") (pintype "passive"))
      (node (ref "D8") (pin "1") (pinfunction "K_1") (pintype "passive"))
      (node (ref "D9") (pin "1") (pinfunction "K_1") (pintype "passive"))
    )
    (net (code "23") (name "/Row1") (class "Default")
      (node (ref "D22") (pin "1") (pinfunction "K_1") (pintype "passive"))
      (node (ref "D23") (pin "1") (pinfunction "K_1") (pintype "passive"))
      (node (ref "D24") (pin "1") (pinfunction "K_1") (pintype "passive"))
      (node (ref "D25") (pin "1") (pinfunction "K_1") (pintype "passive"))
      (node (ref "D26") (pin "1") (pinfunction "K_1") (pintype "passive"))
      (node (ref "D27") (pin "1") (pinfunction "K_1") (pintype "passive"))
      (node (ref "D28") (pin "1") (pinfunction "K_1") (pintype "passive"))
      (node (ref "D29") (pin "1") (pinfunction "K_1") (pintype "passive"))
      (node (ref "D30") (pin "1") (pinfunction "K_1") (pintype "passive"))
      (node (ref "D31") (pin "1") (pinfunction "K_1") (pintype "passive"))
      (node (ref "D32") (pin "1") (pinfunction "K_1") (pintype "passive"))
      (node (ref "D33") (pin "1") (pinfunction "K_1") (pintype "passive"))
      (node (ref "D34") (pin "1") (pinfunction "K_1") (pintype "passive"))
      (node (ref "D35") (pin "1") (pinfunction "K_1") (pintype "passive"))
      (node (ref "D36") (pin "1") (pinfunction "K_1") (pintype "passive"))
      (node (ref "D37") (pin "1") (pinfunction "K_1") (pintype "passive"))
      (node (ref "D38") (pin "1") (pinfunction "K_1") (pintype "passive"))
      (node (ref "D39") (pin "1") (pinfunction "K_1") (pintype "passive"))
      (node (ref "D40") (pin "1") (pinfunction "K_1") (pintype "passive"))
      (node (ref "D41") (pin "1") (pinfunction "K_1") (pintype "passive"))
      (node (ref "D42") (pin "1") (pinfunction "K_1") (pintype "passive"))
    )
    (net (code "24") (name "/Row2") (class "Default")
      (node (ref "D43") (pin "1") (pinfunction "K_1") (pintype "passive"))
      (node (ref "D44") (pin "1") (pinfunction "K_1") (pintype "passive"))
      (node (ref "D45") (pin "1") (pinfunction "K_1") (pintype "passive"))
      (node (ref "D46") (pin "1") (pinfunction "K_1") (pintype "passive"))
      (node (ref "D47") (pin "1") (pinfunction "K_1") (pintype "passive"))
      (node (ref "D48") (pin "1") (pinfunction "K_1") (pintype "passive"))
      (node (ref "D49") (pin "1") (pinfunction "K_1") (pintype "passive"))
      (node (ref "D50") (pin "1") (pinfunction "K_1") (pintype "passive"))
      (node (ref "D51") (pin "1") (pinfunction "K_1") (pintype "passive"))
      (node (ref "D52") (pin "1") (pinfunction "K_1") (pintype "passive"))
      (node (ref "D53") (pin "1") (pinfunction "K_1") (pintype "passive"))
      (node (ref "D54") (pin "1") (pinfunction "K_1") (pintype "passive"))
      (node (ref "D55") (pin "1") (pinfunction "K_1") (pintype "passive"))
      (node (ref "D56") (pin "1") (pinfunction "K_1") (pintype "passive"))
      (node (ref "D57") (pin "1") (pinfunction "K_1") (pintype "passive"))
      (node (ref "D58") (pin "1") (pinfunction "K_1") (pintype "passive"))
      (node (ref "D59") (pin "1") (pinfunction "K_1") (pintype "passive"))
      (node (ref "D60") (pin "1") (pinfunction "K_1") (pintype "passive"))
      (node (ref "D61") (pin "1") (pinfunction "K_1") (pintype "passive"))
      (node (ref "D62") (pin "1") (pinfunction "K_1") (pintype "passive"))
      (node (ref "D63") (pin "1") (pinfunction "K_1") (pintype "passive"))
    )
    (net (code "25") (name "/Row3") (class "Default")
      (node (ref "D64") (pin "1") (pinfunction "K_1") (pintype "passive"))
      (node (ref "D65") (pin "1") (pinfunction "K_1") (pintype "passive"))
      (node (ref "D66") (pin "1") (pinfunction "K_1") (pintype "passive"))
      (node (ref "D67") (pin "1") (pinfunction "K_1") (pintype "passive"))
      (node (ref "D68") (pin "1") (pinfunction "K_1") (pintype "passive"))
      (node (ref "D69") (pin "1") (pinfunction "K_1") (pintype "passive"))
      (node (ref "D70") (pin "1") (pinfunction "K_1") (pintype "passive"))
      (node (ref "D71") (pin "1") (pinfunction "K_1") (pintype "passive"))
      (node (ref "D72") (pin "1") (pinfunction "K_1") (pintype "passive"))
      (node (ref "D73") (pin "1") (pinfunction "K_1") (pintype "passive"))
      (node (ref "D74") (pin "1") (pinfunction "K_1") (pintype "passive"))
      (node (ref "D75") (pin "1") (pinfunction "K_1") (pintype "passive"))
      (node (ref "D76") (pin "1") (pinfunction "K_1") (pintype "passive"))
      (node (ref "D77") (pin "1") (pinfunction "K_1") (pintype "passive"))
      (node (ref "D78") (pin "1") (pinfunction "K_1") (pintype "passive"))
      (node (ref "D79") (pin "1") (pinfunction "K_1") (pintype "passive"))
      (node (ref "D80") (pin "1") (pinfunction "K_1") (pintype "passive"))
      (node (ref "D81") (pin "1") (pinfunction "K_1") (pintype "passive"))
      (node (ref "D82") (pin "1") (pinfunction "K_1") (pintype "passive"))
      (node (ref "D83") (pin "1") (pinfunction "K_1") (pintype "passive"))
      (node (ref "D84") (pin "1") (pinfunction "K_1") (pintype "passive"))
    )
    (net (code "26") (name "/Row4") (class "Default")
      (node (ref "D100") (pin "1") (pinfunction "K_1") (pintype "passive"))
      (node (ref "D101") (pin "1") (pinfunction "K_1") (pintype "passive"))
      (node (ref "D102") (pin "1") (pinfunction "K_1") (pintype "passive"))
      (node (ref "D103") (pin "1") (pinfunction "K_1") (pintype "passive"))
      (node (ref "D104") (pin "1") (pinfunction "K_1") (pintype "passive"))
      (node (ref "D105") (pin "1") (pinfunction "K_1") (pintype "passive"))
      (node (ref "D85") (pin "1") (pinfunction "K_1") (pintype "passive"))
      (node (ref "D86") (pin "1") (pinfunction "K_1") (pintype "passive"))
      (node (ref "D87") (pin "1") (pinfunction "K_1") (pintype "passive"))
      (node (ref "D88") (pin "1") (pinfunction "K_1") (pintype "passive"))
      (node (ref "D89") (pin "1") (pinfunction "K_1") (pintype "passive"))
      (node (ref "D90") (pin "1") (pinfunction "K_1") (pintype "passive"))
      (node (ref "D91") (pin "1") (pinfunction "K_1") (pintype "passive"))
      (node (ref "D92") (pin "1") (pinfunction "K_1") (pintype "passive"))
      (node (ref "D93") (pin "1") (pinfunction "K_1") (pintype "passive"))
      (node (ref "D94") (pin "1") (pinfunction "K_1") (pintype "passive"))
      (node (ref "D95") (pin "1") (pinfunction "K_1") (pintype "passive"))
      (node (ref "D96") (pin "1") (pinfunction "K_1") (pintype "passive"))
      (node (ref "D97") (pin "1") (pinfunction "K_1") (pintype "passive"))
      (node (ref "D98") (pin "1") (pinfunction "K_1") (pintype "passive"))
      (node (ref "D99") (pin "1") (pinfunction "K_1") (pintype "passive"))
    )
    (net (code "27") (name "/Row5") (class "Default")
      (node (ref "D106") (pin "1") (pinfunction "K_1") (pintype "passive"))
      (node (ref "D107") (pin "1") (pinfunction "K_1") (pintype "passive"))
      (node (ref "D108") (pin "1") (pinfunction "K_1") (pintype "passive"))
      (node (ref "D109") (pin "1") (pinfunction "K_1") (pintype "passive"))
      (node (ref "D110") (pin "1") (pinfunction "K_1") (pintype "passive"))
      (node (ref "D111") (pin "1") (pinfunction "K_1") (pintype "passive"))
      (node (ref "D112") (pin "1") (pinfunction "K_1") (pintype "passive"))
      (node (ref "D113") (pin "1") (pinfunction "K_1") (pintype "passive"))
      (node (ref "D114") (pin "1") (pinfunction "K_1") (pintype "passive"))
      (node (ref "D115") (pin "1") (pinfunction "K_1") (pintype "passive"))
      (node (ref "D116") (pin "1") (pinfunction "K_1") (pintype "passive"))
      (node (ref "D117") (pin "1") (pinfunction "K_1") (pintype "passive"))
      (node (ref "D118") (pin "1") (pinfunction "K_1") (pintype "passive"))
      (node (ref "D119") (pin "1") (pinfunction "K_1") (pintype "passive"))
      (node (ref "D120") (pin "1") (pinfunction "K_1") (pintype "passive"))
      (node (ref "D121") (pin "1") (pinfunction "K_1") (pintype "passive"))
      (node (ref "D122") (pin "1") (pinfunction "K_1") (pintype "passive"))
      (node (ref "D123") (pin "1") (pinfunction "K_1") (pintype "passive"))
      (node (ref "D124") (pin "1") (pinfunction "K_1") (pintype "passive"))
      (node (ref "D125") (pin "1") (pinfunction "K_1") (pintype "passive"))
      (node (ref "D126") (pin "1") (pinfunction "K_1") (pintype "passive"))
    )
    (net (code "28") (name "Net-(D1-A)") (class "Default")
      (node (ref "D1") (pin "2") (pinfunction "A_2") (pintype "passive"))
      (node (ref "SW1") (pin "1") (pinfunction "1_1") (pintype "passive"))
    )
    (net (code "29") (name "Net-(D2-A)") (class "Default")
      (node (ref "D2") (pin "2") (pinfunction "A_2") (pintype "passive"))
      (node (ref "SW2") (pin "1") (pinfunction "1_1") (pintype "passive"))
    )
    (net (code "30") (name "Net-(D3-A)") (class "Default")
      (node (ref "D3") (pin "2") (pinfunction "A_2") (pintype "passive"))
      (node (ref "SW3") (pin "1") (pinfunction "1_1") (pintype "passive"))
    )
    (net (code "31") (name "Net-(D4-A)") (class "Default")
      (node (ref "D4") (pin "2") (pinfunction "A_2") (pintype "passive"))
      (node (ref "SW4") (pin "1") (pinfunction "1_1") (pintype "passive"))
    )
    (net (code "32") (name "Net-(D5-A)") (class "Default")
      (node (ref "D5") (pin "2") (pinfunction "A_2") (pintype "passive"))
      (node (ref "SW5") (pin "1") (pinfunction "1_1") (pintype "passive"))
    )
    (net (code "33") (name "Net-(D6-A)") (class "Default")
      (node (ref "D6") (pin "2") (pinfunction "A_2") (pintype "passive"))
      (node (ref "SW6") (pin "1") (pinfunction "1_1") (pintype "passive"))
    )
    (net (code "34") (name "Net-(D7-A)") (class "Default")
      (node (ref "D7") (pin "2") (pinfunction "A_2") (pintype "passive"))
      (node (ref "SW7") (pin "1") (pinfunction "1_1") (pintype "passive"))
    )
    (net (code "35") (name "Net-(D8-A)") (class "Default")
      (node (ref "D8") (pin "2") (pinfunction "A_2") (pintype "passive"))
      (node (ref "SW8") (pin "1") (pinfunction "1_1") (pintype "passive"))
    )
    (net (code "36") (name "Net-(D9-A)") (class "Default")
      (node (ref "D9") (pin "2") (pinfunction "A_2") (pintype "passive"))
      (node (ref "SW9") (pin "1") (pinfunction "1_1") (pintype "passive"))
    )
    (net (code "37") (name "Net-(D10-A)") (class "Default")
      (node (ref "D10") (pin "2") (pinfunction "A_2") (pintype "passive"))
      (node (ref "SW10") (pin "1") (pinfunction "1_1") (pintype "passive"))
    )
    (net (code "38") (name "Net-(D11-A)") (class "Default")
      (node (ref "D11") (pin "2") (pinfunction "A_2") (pintype "passive"))
      (node (ref "SW11") (pin "1") (pinfunction "1_1") (pintype "passive"))
    )
    (net (code "39") (name "Net-(D12-A)") (class "Default")
      (node (ref "D12") (pin "2") (pinfunction "A_2") (pintype "passive"))
      (node (ref "SW12") (pin "1") (pinfunction "1_1") (pintype "passive"))
    )
    (net (code "40") (name "Net-(D13-A)") (class "Default")
      (node (ref "D13") (pin "2") (pinfunction "A_2") (pintype "passive"))
      (node (ref "SW13") (pin "1") (pinfunction "1_1") (pintype "passive"))
    )
    (net (code "41") (name "Net-(D14-A)") (class "Default")
      (node (ref "D14") (pin "2") (pinfunction "A_2") (pintype "passive"))
      (node (ref "SW14") (pin "1") (pinfunction "1_1") (pintype "passive"))
    )
    (net (code "42") (name "Net-(D15-A)") (class "Default")
      (node (ref "D15") (pin "2") (pinfunction "A_2") (pintype "passive"))
      (node (ref "SW15") (pin "1") (pinfunction "1_1") (pintype "passive"))
    )
    (net (code "43") (name "Net-(D16-A)") (class "Default")
      (node (ref "D16") (pin "2") (pinfunction "A_2") (pintype "passive"))
      (node (ref "SW16") (pin "1") (pinfunction "1_1") (pintype "passive"))
    )
    (net (code "44") (name "Net-(D17-A)") (class "Default")
      (node (ref "D17") (pin "2") (pinfunction "A_2") (pintype "passive"))
      (node (ref "SW17") (pin "1") (pinfunction "1_1") (pintype "passive"))
    )
    (net (code "45") (name "Net-(D18-A)") (class "Default")
      (node (ref "D18") (pin "2") (pinfunction "A_2") (pintype "passive"))
      (node (ref "SW18") (pin "1") (pinfunction "1_1") (pintype "passive"))
    )
    (net (code "46") (name "Net-(D19-A)") (class "Default")
      (node (ref "D19") (pin "2") (pinfunction "A_2") (pintype "passive"))
      (node (ref "SW19") (pin "1") (pinfunction "1_1") (pintype "passive"))
    )
    (net (code "47") (name "Net-(D20-A)") (class "Default")
      (node (ref "D20") (pin "2") (pinfunction "A_2") (pintype "passive"))
      (node (ref "SW20") (pin "1") (pinfunction "1_1") (pintype "passive"))
    )
    (net (code "48") (name "Net-(D21-A)") (class "Default")
      (node (ref "D21") (pin "2") (pinfunction "A_2") (pintype "passive"))
      (node (ref "SW21") (pin "1") (pinfunction "1_1") (pintype "passive"))
    )
    (net (code "49") (name "Net-(D22-A)") (class "Default")
      (node (ref "D22") (pin "2") (pinfunction "A_2") (pintype "passive"))
      (node (ref "SW22") (pin "1") (pinfunction "1_1") (pintype "passive"))
    )
    (net (code "50") (name "Net-(D23-A)") (class "Default")
      (node (ref "D23") (pin "2") (pinfunction "A_2") (pintype "passive"))
      (node (ref "SW23") (pin "1") (pinfunction "1_1") (pintype "passive"))
    )
    (net (code "51") (name "Net-(D24-A)") (class "Default")
      (node (ref "D24") (pin "2") (pinfunction "A_2") (pintype "passive"))
      (node (ref "SW24") (pin "1") (pinfunction "1_1") (pintype "passive"))
    )
    (net (code "52") (name "Net-(D25-A)") (class "Default")
      (node (ref "D25") (pin "2") (pinfunction "A_2") (pintype "passive"))
      (node (ref "SW25") (pin "1") (pinfunction "1_1") (pintype "passive"))
    )
    (net (code "53") (name "Net-(D26-A)") (class "Default")
      (node (ref "D26") (pin "2") (pinfunction "A_2") (pintype "passive"))
      (node (ref "SW26") (pin "1") (pinfunction "1_1") (pintype "passive"))
    )
    (net (code "54") (name "Net-(D27-A)") (class "Default")
      (node (ref "D27") (pin "2") (pinfunction "A_2") (pintype "passive"))
      (node (ref "SW27") (pin "1") (pinfunction "1_1") (pintype "passive"))
    )
    (net (code "55") (name "Net-(D28-A)") (class "Default")
      (node (ref "D28") (pin "2") (pinfunction "A_2") (pintype "passive"))
      (node (ref "SW28") (pin "1") (pinfunction "1_1") (pintype "passive"))
    )
    (net (code "56") (name "Net-(D29-A)") (class "Default")
      (node (ref "D29") (pin "2") (pinfunction "A_2") (pintype "passive"))
      (node (ref "SW29") (pin "1") (pinfunction "1_1") (pintype "passive"))
    )
    (net (code "57") (name "Net-(D30-A)") (class "Default")
      (node (ref "D30") (pin "2") (pinfunction "A_2") (pintype "passive"))
      (node (ref "SW30") (pin "1") (pinfunction "1_1") (pintype "passive"))
    )
    (net (code "58") (name "Net-(D31-A)") (class "Default")
      (node (ref "D31") (pin "2") (pinfunction "A_2") (pintype "passive"))
      (node (ref "SW31") (pin "1") (pinfunction "1_1") (pintype "passive"))
    )
    (net (code "59") (name "Net-(D32-A)") (class "Default")
      (node (ref "D32") (pin "2") (pinfunction "A_2") (pintype "passive"))
      (node (ref "SW32") (pin "1") (pinfunction "1_1") (pintype "passive"))
    )
    (net (code "60") (name "Net-(D33-A)") (class "Default")
      (node (ref "D33") (pin "2") (pinfunction "A_2") (pintype "passive"))
      (node (ref "SW33") (pin "1") (pinfunction "1_1") (pintype "passive"))
    )
    (net (code "61") (name "Net-(D34-A)") (class "Default")
      (node (ref "D34") (pin "2") (pinfunction "A_2") (pintype "passive"))
      (node (ref "SW34") (pin "1") (pinfunction "1_1") (pintype "passive"))
    )
    (net (code "62") (name "Net-(D35-A)") (class "Default")
      (node (ref "D35") (pin "2") (pinfunction "A_2") (pintype "passive"))
      (node (ref "SW35") (pin "1") (pinfunction "1_1") (pintype "passive"))
    )
    (net (code "63") (name "Net-(D36-A)") (class "Default")
      (node (ref "D36") (pin "2") (pinfunction "A_2") (pintype "passive"))
      (node (ref "SW36") (pin "1") (pinfunction "1_1") (pintype "passive"))
    )
    (net (code "64") (name "Net-(D37-A)") (class "Default")
      (node (ref "D37") (pin "2") (pinfunction "A_2") (pintype "passive"))
      (node (ref "SW37") (pin "1") (pinfunction "1_1") (pintype "passive"))
    )
    (net (code "65") (name "Net-(D38-A)") (class "Default")
      (node (ref "D38") (pin "2") (pinfunction "A_2") (pintype "passive"))
      (node (ref "SW38") (pin "1") (pinfunction "1_1") (pintype "passive"))
    )
    (net (code "66") (name "Net-(D39-A)") (class "Default")
      (node (ref "D39") (pin "2") (pinfunction "A_2") (pintype "passive"))
      (node (ref "SW39") (pin "1") (pinfunction "1_1") (pintype "passive"))
    )
    (net (code "67") (name "Net-(D40-A)") (class "Default")
      (node (ref "D40") (pin "2") (pinfunction "A_2") (pintype "passive"))
      (node (ref "SW40") (pin "1") (pinfunction "1_1") (pintype "passive"))
    )
    (net (code "68") (name "Net-(D41-A)") (class "Default")
      (node (ref "D41") (pin "2") (pinfunction "A_2") (pintype "passive"))
      (node (ref "SW41") (pin "1") (pinfunction "1_1") (pintype "passive"))
    )
    (net (code "69") (name "Net-(D42-A)") (class "Default")
      (node (ref "D42") (pin "2") (pinfunction "A_2") (pintype "passive"))
      (node (ref "SW42") (pin "1") (pinfunction "1_1") (pintype "passive"))
    )
    (net (code "70") (name "Net-(D43-A)") (class "Default")
      (node (ref "D43") (pin "2") (pinfunction "A_2") (pintype "passive"))
      (node (ref "SW43") (pin "1") (pinfunction "1_1") (pintype "passive"))
    )
    (net (code "71") (name "Net-(D44-A)") (class "Default")
      (node (ref "D44") (pin "2") (pinfunction "A_2") (pintype "passive"))
      (node (ref "SW44") (pin "1") (pinfunction "1_1") (pintype "passive"))
    )
    (net (code "72") (name "Net-(D45-A)") (class "Default")
      (node (ref "D45") (pin "2") (pinfunction "A_2") (pintype "passive"))
      (node (ref "SW45") (pin "1") (pinfunction "1_1") (pintype "passive"))
    )
    (net (code "73") (name "Net-(D46-A)") (class "Default")
      (node (ref "D46") (pin "2") (pinfunction "A_2") (pintype "passive"))
      (node (ref "SW46") (pin "1") (pinfunction "1_1") (pintype "passive"))
    )
    (net (code "74") (name "Net-(D47-A)") (class "Default")
      (node (ref "D47") (pin "2") (pinfunction "A_2") (pintype "passive"))
      (node (ref "SW47") (pin "1") (pinfunction "1_1") (pintype "passive"))
    )
    (net (code "75") (name "Net-(D48-A)") (class "Default")
      (node (ref "D48") (pin "2") (pinfunction "A_2") (pintype "passive"))
      (node (ref "SW48") (pin "1") (pinfunction "1_1") (pintype "passive"))
    )
    (net (code "76") (name "Net-(D49-A)") (class "Default")
      (node (ref "D49") (pin "2") (pinfunction "A_2") (pintype "passive"))
      (node (ref "SW49") (pin "1") (pinfunction "1_1") (pintype "passive"))
    )
    (net (code "77") (name "Net-(D50-A)") (class "Default")
      (node (ref "D50") (pin "2") (pinfunction "A_2") (pintype "passive"))
      (node (ref "SW50") (pin "1") (pinfunction "1_1") (pintype "passive"))
    )
    (net (code "78") (name "Net-(D51-A)") (class "Default")
      (node (ref "D51") (pin "2") (pinfunction "A_2") (pintype "passive"))
      (node (ref "SW51") (pin "1") (pinfunction "1_1") (pintype "passive"))
    )
    (net (code "79") (name "Net-(D52-A)") (class "Default")
      (node (ref "D52") (pin "2") (pinfunction "A_2") (pintype "passive"))
      (node (ref "SW52") (pin "1") (pinfunction "1_1") (pintype "passive"))
    )
    (net (code "80") (name "Net-(D53-A)") (class "Default")
      (node (ref "D53") (pin "2") (pinfunction "A_2") (pintype "passive"))
      (node (ref "SW53") (pin "1") (pinfunction "1_1") (pintype "passive"))
    )
    (net (code "81") (name "Net-(D54-A)") (class "Default")
      (node (ref "D54") (pin "2") (pinfunction "A_2") (pintype "passive"))
      (node (ref "SW54") (pin "1") (pinfunction "1_1") (pintype "passive"))
    )
    (net (code "82") (name "Net-(D55-A)") (class "Default")
      (node (ref "D55") (pin "2") (pinfunction "A_2") (pintype "passive"))
      (node (ref "SW55") (pin "1") (pinfunction "1_1") (pintype "passive"))
    )
    (net (code "83") (name "Net-(D56-A)") (class "Default")
      (node (ref "D56") (pin "2") (pinfunction "A_2") (pintype "passive"))
      (node (ref "SW56") (pin "1") (pinfunction "1_1") (pintype "passive"))
    )
    (net (code "84") (name "Net-(D57-A)") (class "Default")
      (node (ref "D57") (pin "2") (pinfunction "A_2") (pintype "passive"))
      (node (ref "SW57") (pin "1") (pinfunction "1_1") (pintype "passive"))
    )
    (net (code "85") (name "Net-(D58-A)") (class "Default")
      (node (ref "D58") (pin "2") (pinfunction "A_2") (pintype "passive"))
      (node (ref "SW58") (pin "1") (pinfunction "1_1") (pintype "passive"))
    )
    (net (code "86") (name "Net-(D59-A)") (class "Default")
      (node (ref "D59") (pin "2") (pinfunction "A_2") (pintype "passive"))
      (node (ref "SW59") (pin "1") (pinfunction "1_1") (pintype "passive"))
    )
    (net (code "87") (name "Net-(D60-A)") (class "Default")
      (node (ref "D60") (pin "2") (pinfunction "A_2") (pintype "passive"))
      (node (ref "SW60") (pin "1") (pinfunction "1_1") (pintype "passive"))
    )
    (net (code "88") (name "Net-(D61-A)") (class "Default")
      (node (ref "D61") (pin "2") (pinfunction "A_2") (pintype "passive"))
      (node (ref "SW61") (pin "1") (pinfunction "1_1") (pintype "passive"))
    )
    (net (code "89") (name "Net-(D62-A)") (class "Default")
      (node (ref "D62") (pin "2") (pinfunction "A_2") (pintype "passive"))
      (node (ref "SW62") (pin "1") (pinfunction "1_1") (pintype "passive"))
    )
    (net (code "90") (name "Net-(D63-A)") (class "Default")
      (node (ref "D63") (pin "2") (pinfunction "A_2") (pintype "passive"))
      (node (ref "SW63") (pin "1") (pinfunction "1_1") (pintype "passive"))
    )
    (net (code "91") (name "Net-(D64-A)") (class "Default")
      (node (ref "D64") (pin "2") (pinfunction "A_2") (pintype "passive"))
      (node (ref "SW64") (pin "1") (pinfunction "1_1") (pintype "passive"))
    )
    (net (code "92") (name "Net-(D65-A)") (class "Default")
      (node (ref "D65") (pin "2") (pinfunction "A_2") (pintype "passive"))
      (node (ref "SW65") (pin "1") (pinfunction "1_1") (pintype "passive"))
    )
    (net (code "93") (name "Net-(D66-A)") (class "Default")
      (node (ref "D66") (pin "2") (pinfunction "A_2") (pintype "passive"))
      (node (ref "SW66") (pin "1") (pinfunction "1_1") (pintype "passive"))
    )
    (net (code "94") (name "Net-(D67-A)") (class "Default")
      (node (ref "D67") (pin "2") (pinfunction "A_2") (pintype "passive"))
      (node (ref "SW67") (pin "1") (pinfunction "1_1") (pintype "passive"))
    )
    (net (code "95") (name "Net-(D68-A)") (class "Default")
      (node (ref "D68") (pin "2") (pinfunction "A_2") (pintype "passive"))
      (node (ref "SW68") (pin "1") (pinfunction "1_1") (pintype "passive"))
    )
    (net (code "96") (name "Net-(D69-A)") (class "Default")
      (node (ref "D69") (pin "2") (pinfunction "A_2") (pintype "passive"))
      (node (ref "SW69") (pin "1") (pinfunction "1_1") (pintype "passive"))
    )
    (net (code "97") (name "Net-(D70-A)") (class "Default")
      (node (ref "D70") (pin "2") (pinfunction "A_2") (pintype "passive"))
      (node (ref "SW70") (pin "1") (pinfunction "1_1") (pintype "passive"))
    )
    (net (code "98") (name "Net-(D71-A)") (class "Default")
      (node (ref "D71") (pin "2") (pinfunction "A_2") (pintype "passive"))
      (node (ref "SW71") (pin "1") (pinfunction "1_1") (pintype "passive"))
    )
    (net (code "99") (name "Net-(D72-A)") (class "Default")
      (node (ref "D72") (pin "2") (pinfunction "A_2") (pintype "passive"))
      (node (ref "SW72") (pin "1") (pinfunction "1_1") (pintype "passive"))
    )
    (net (code "100") (name "Net-(D73-A)") (class "Default")
      (node (ref "D73") (pin "2") (pinfunction "A_2") (pintype "passive"))
      (node (ref "SW73") (pin "1") (pinfunction "1_1") (pintype "passive"))
    )
    (net (code "101") (name "Net-(D74-A)") (class "Default")
      (node (ref "D74") (pin "2") (pinfunction "A_2") (pintype "passive"))
      (node (ref "SW74") (pin "1") (pinfunction "1_1") (pintype "passive"))
    )
    (net (code "102") (name "Net-(D75-A)") (class "Default")
      (node (ref "D75") (pin "2") (pinfunction "A_2") (pintype "passive"))
      (node (ref "SW75") (pin "1") (pinfunction "1_1") (pintype "passive"))
    )
    (net (code "103") (name "Net-(D76-A)") (class "Default")
      (node (ref "D76") (pin "2") (pinfunction "A_2") (pintype "passive"))
      (node (ref "SW76") (pin "1") (pinfunction "1_1") (pintype "passive"))
    )
    (net (code "104") (name "Net-(D77-A)") (class "Default")
      (node (ref "D77") (pin "2") (pinfunction "A_2") (pintype "passive"))
      (node (ref "SW77") (pin "1") (pinfunction "1_1") (pintype "passive"))
    )
    (net (code "105") (name "Net-(D78-A)") (class "Default")
      (node (ref "D78") (pin "2") (pinfunction "A_2") (pintype "passive"))
      (node (ref "SW78") (pin "1") (pinfunction "1_1") (pintype "passive"))
    )
    (net (code "106") (name "Net-(D79-A)") (class "Default")
      (node (ref "D79") (pin "2") (pinfunction "A_2") (pintype "passive"))
      (node (ref "SW79") (pin "1") (pinfunction "1_1") (pintype "passive"))
    )
    (net (code "107") (name "Net-(D80-A)") (class "Default")
      (node (ref "D80") (pin "2") (pinfunction "A_2") (pintype "passive"))
      (node (ref "SW80") (pin "1") (pinfunction "1_1") (pintype "passive"))
    )
    (net (code "108") (name "Net-(D81-A)") (class "Default")
      (node (ref "D81") (pin "2") (pinfunction "A_2") (pintype "passive"))
      (node (ref "SW81") (pin "1") (pinfunction "1_1") (pintype "passive"))
    )
    (net (code "109") (name "Net-(D82-A)") (class "Default")
      (node (ref "D82") (pin "2") (pinfunction "A_2") (pintype "passive"))
      (node (ref "SW82") (pin "1") (pinfunction "1_1") (pintype "passive"))
    )
    (net (code "110") (name "Net-(D83-A)") (class "Default")
      (node (ref "D83") (pin "2") (pinfunction "A_2") (pintype "passive"))
      (node (ref "SW83") (pin "1") (pinfunction "1_1") (pintype "passive"))
    )
    (net (code "111") (name "Net-(D84-A)") (class "Default")
      (node (ref "D84") (pin "2") (pinfunction "A_2") (pintype "passive"))
      (node (ref "SW84") (pin "1") (pinfunction "1_1") (pintype "passive"))
    )
    (net (code "112") (name "Net-(D85-A)") (class "Default")
      (node (ref "D85") (pin "2") (pinfunction "A_2") (pintype "passive"))
      (node (ref "SW85") (pin "1") (pinfunction "1_1") (pintype "passive"))
    )
    (net (code "113") (name "Net-(D86-A)") (class "Default")
      (node (ref "D86") (pin "2") (pinfunction "A_2") (pintype "passive"))
      (node (ref "SW86") (pin "1") (pinfunction "1_1") (pintype "passive"))
    )
    (net (code "114") (name "Net-(D87-A)") (class "Default")
      (node (ref "D87") (pin "2") (pinfunction "A_2") (pintype "passive"))
      (node (ref "SW87") (pin "1") (pinfunction "1_1") (pintype "passive"))
    )
    (net (code "115") (name "Net-(D88-A)") (class "Default")
      (node (ref "D88") (pin "2") (pinfunction "A_2") (pintype "passive"))
      (node (ref "SW88") (pin "1") (pinfunction "1_1") (pintype "passive"))
    )
    (net (code "116") (name "Net-(D89-A)") (class "Default")
      (node (ref "D89") (pin "2") (pinfunction "A_2") (pintype "passive"))
      (node (ref "SW89") (pin "1") (pinfunction "1_1") (pintype "passive"))
    )
    (net (code "117") (name "Net-(D90-A)") (class "Default")
      (node (ref "D90") (pin "2") (pinfunction "A_2") (pintype "passive"))
      (node (ref "SW90") (pin "1") (pinfunction "1_1") (pintype "passive"))
    )
    (net (code "118") (name "Net-(D91-A)") (class "Default")
      (node (ref "D91") (pin "2") (pinfunction "A_2") (pintype "passive"))
      (node (ref "SW91") (pin "1") (pinfunction "1_1") (pintype "passive"))
    )
    (net (code "119") (name "Net-(D92-A)") (class "Default")
      (node (ref "D92") (pin "2") (pinfunction "A_2") (pintype "passive"))
      (node (ref "SW92") (pin "1") (pinfunction "1_1") (pintype "passive"))
    )
    (net (code "120") (name "Net-(D93-A)") (class "Default")
      (node (ref "D93") (pin "2") (pinfunction "A_2") (pintype "passive"))
      (node (ref "SW93") (pin "1") (pinfunction "1_1") (pintype "passive"))
    )
    (net (code "121") (name "Net-(D94-A)") (class "Default")
      (node (ref "D94") (pin "2") (pinfunction "A_2") (pintype "passive"))
      (node (ref "SW94") (pin "1") (pinfunction "1_1") (pintype "passive"))
    )
    (net (code "122") (name "Net-(D95-A)") (class "Default")
      (node (ref "D95") (pin "2") (pinfunction "A_2") (pintype "passive"))
      (node (ref "SW95") (pin "1") (pinfunction "1_1") (pintype "passive"))
    )
    (net (code "123") (name "Net-(D96-A)") (class "Default")
      (node (ref "D96") (pin "2") (pinfunction "A_2") (pintype "passive"))
      (node (ref "SW96") (pin "1") (pinfunction "1_1") (pintype "passive"))
    )
    (net (code "124") (name "Net-(D97-A)") (class "Default")
      (node (ref "D97") (pin "2") (pinfunction "A_2") (pintype "passive"))
      (node (ref "SW97") (pin "1") (pinfunction "1_1") (pintype "passive"))
    )
    (net (code "125") (name "Net-(D98-A)") (class "Default")
      (node (ref "D98") (pin "2") (pinfunction "A_2") (pintype "passive"))
      (node (ref "SW98") (pin "1") (pinfunction "1_1") (pintype "passive"))
    )
    (net (code "126") (name "Net-(D99-A)") (class "Default")
      (node (ref "D99") (pin "2") (pinfunction "A_2") (pintype "passive"))
      (node (ref "SW99") (pin "1") (pinfunction "1_1") (pintype "passive"))
    )
    (net (code "127") (name "Net-(D100-A)") (class "Default")
      (node (ref "D100") (pin "2") (pinfunction "A_2") (pintype "passive"))
      (node (ref "SW100") (pin "1") (pinfunction "1_1") (pintype "passive"))
    )
    (net (code "128") (name "Net-(D101-A)") (class "Default")
      (node (ref "D101") (pin "2") (pinfunction "A_2") (pintype "passive"))
      (node (ref "SW101") (pin "1") (pinfunction "1_1") (pintype "passive"))
    )
    (net (code "129") (name "Net-(D102-A)") (class "Default")
      (node (ref "D102") (pin "2") (pinfunction "A_2") (pintype "passive"))
      (node (ref "SW102") (pin "1") (pinfunction "1_1") (pintype "passive"))
    )
    (net (code "130") (name "Net-(D103-A)") (class "Default")
      (node (ref "D103") (pin "2") (pinfunction "A_2") (pintype "passive"))
      (node (ref "SW103") (pin "1") (pinfunction "1_1") (pintype "passive"))
    )
    (net (code "131") (name "Net-(D104-A)") (class "Default")
      (node (ref "D104") (pin "2") (pinfunction "A_2") (pintype "passive"))
      (node (ref "SW104") (pin "1") (pinfunction "1_1") (pintype "passive"))
    )
    (net (code "132") (name "Net-(D105-A)") (class "Default")
      (node (ref "D105") (pin "2") (pinfunction "A_2") (pintype "passive"))
      (node (ref "SW105") (pin "1") (pinfunction "1_1") (pintype "passive"))
    )
    (net (code "133") (name "Net-(D106-A)") (class "Default")
      (node (ref "D106") (pin "2") (pinfunction "A_2") (pintype "passive"))
      (node (ref "SW106") (pin "1") (pinfunction "1_1") (pintype "passive"))
    )
    (net (code "134") (name "Net-(D107-A)") (class "Default")
      (node (ref "D107") (pin "2") (pinfunction "A_2") (pintype "passive"))
      (node (ref "SW107") (pin "1") (pinfunction "1_1") (pintype "passive"))
    )
    (net (code "135") (name "Net-(D108-A)") (class "Default")
      (node (ref "D108") (pin "2") (pinfunction "A_2") (pintype "passive"))
      (node (ref "SW108") (pin "1") (pinfunction "1_1") (pintype "passive"))
    )
    (net (code "136") (name "Net-(D109-A)") (class "Default")
      (node (ref "D109") (pin "2") (pinfunction "A_2") (pintype "passive"))
      (node (ref "SW109") (pin "1") (pinfunction "1_1") (pintype "passive"))
    )
    (net (code "137") (name "Net-(D110-A)") (class "Default")
      (node (ref "D110") (pin "2") (pinfunction "A_2") (pintype "passive"))
      (node (ref "SW110") (pin "1") (pinfunction "1_1") (pintype "passive"))
    )
    (net (code "138") (name "Net-(D111-A)") (class "Default")
      (node (ref "D111") (pin "2") (pinfunction "A_2") (pintype "passive"))
      (node (ref "SW111") (pin "1") (pinfunction "1_1") (pintype "passive"))
    )
    (net (code "139") (name "Net-(D112-A)") (class "Default")
      (node (ref "D112") (pin "2") (pinfunction "A_2") (pintype "passive"))
      (node (ref "SW112") (pin "1") (pinfunction "1_1") (pintype "passive"))
    )
    (net (code "140") (name "Net-(D113-A)") (class "Default")
      (node (ref "D113") (pin "2") (pinfunction "A_2") (pintype "passive"))
      (node (ref "SW113") (pin "1") (pinfunction "1_1") (pintype "passive"))
    )
    (net (code "141") (name "Net-(D114-A)") (class "Default")
      (node (ref "D114") (pin "2") (pinfunction "A_2") (pintype "passive"))
      (node (ref "SW114") (pin "1") (pinfunction "1_1") (pintype "passive"))
    )
    (net (code "142") (name "Net-(D115-A)") (class "Default")
      (node (ref "D115") (pin "2") (pinfunction "A_2") (pintype "passive"))
      (node (ref "SW115") (pin "1") (pinfunction "1_1") (pintype "passive"))
    )
    (net (code "143") (name "Net-(D116-A)") (class "Default")
      (node (ref "D116") (pin "2") (pinfunction "A_2") (pintype "passive"))
      (node (ref "SW116") (pin "1") (pinfunction "1_1") (pintype "passive"))
    )
    (net (code "144") (name "Net-(D117-A)") (class "Default")
      (node (ref "D117") (pin "2") (pinfunction "A_2") (pintype "passive"))
      (node (ref "SW117") (pin "1") (pinfunction "1_1") (pintype "passive"))
    )
    (net (code "145") (name "Net-(D118-A)") (class "Default")
      (node (ref "D118") (pin "2") (pinfunction "A_2") (pintype "passive"))
      (node (ref "SW118") (pin "1") (pinfunction "1_1") (pintype "passive"))
    )
    (net (code "146") (name "Net-(D119-A)") (class "Default")
      (node (ref "D119") (pin "2") (pinfunction "A_2") (pintype "passive"))
      (node (ref "SW119") (pin "1") (pinfunction "1_1") (pintype "passive"))
    )
    (net (code "147") (name "Net-(D120-A)") (class "Default")
      (node (ref "D120") (pin "2") (pinfunction "A_2") (pintype "passive"))
      (node (ref "SW120") (pin "1") (pinfunction "1_1") (pintype "passive"))
    )
    (net (code "148") (name "Net-(D121-A)") (class "Default")
      (node (ref "D121") (pin "2") (pinfunction "A_2") (pintype "passive"))
      (node (ref "SW121") (pin "1") (pinfunction "1_1") (pintype "passive"))
    )
    (net (code "149") (name "Net-(D122-A)") (class "Default")
      (node (ref "D122") (pin "2") (pinfunction "A_2") (pintype "passive"))
      (node (ref "SW122") (pin "1") (pinfunction "1_1") (pintype "passive"))
    )
    (net (code "150") (name "Net-(D123-A)") (class "Default")
      (node (ref "D123") (pin "2") (pinfunction "A_2") (pintype "passive"))
      (node (ref "SW123") (pin "1") (pinfunction "1_1") (pintype "passive"))
    )
    (net (code "151") (name "Net-(D124-A)") (class "Default")
      (node (ref "D124") (pin "2") (pinfunction "A_2") (pintype "passive"))
      (node (ref "SW124") (pin "1") (pinfunction "1_1") (pintype "passive"))
    )
    (net (code "152") (name "Net-(D125-A)") (class "Default")
      (node (ref "D125") (pin "2") (pinfunction "A_2") (pintype "passive"))
      (node (ref "SW125") (pin "1") (pinfunction "1_1") (pintype "passive"))
    )
    (net (code "153") (name "Net-(D126-A)") (class "Default")
      (node (ref "D126") (pin "2") (pinfunction "A_2") (pintype "passive"))
      (node (ref "SW126") (pin "1") (pinfunction "1_1") (pintype "passive"))
    )
  )
)
